# DBBC7505S-F.net
KiCad netlist of a schematic drawn in Altium Designer
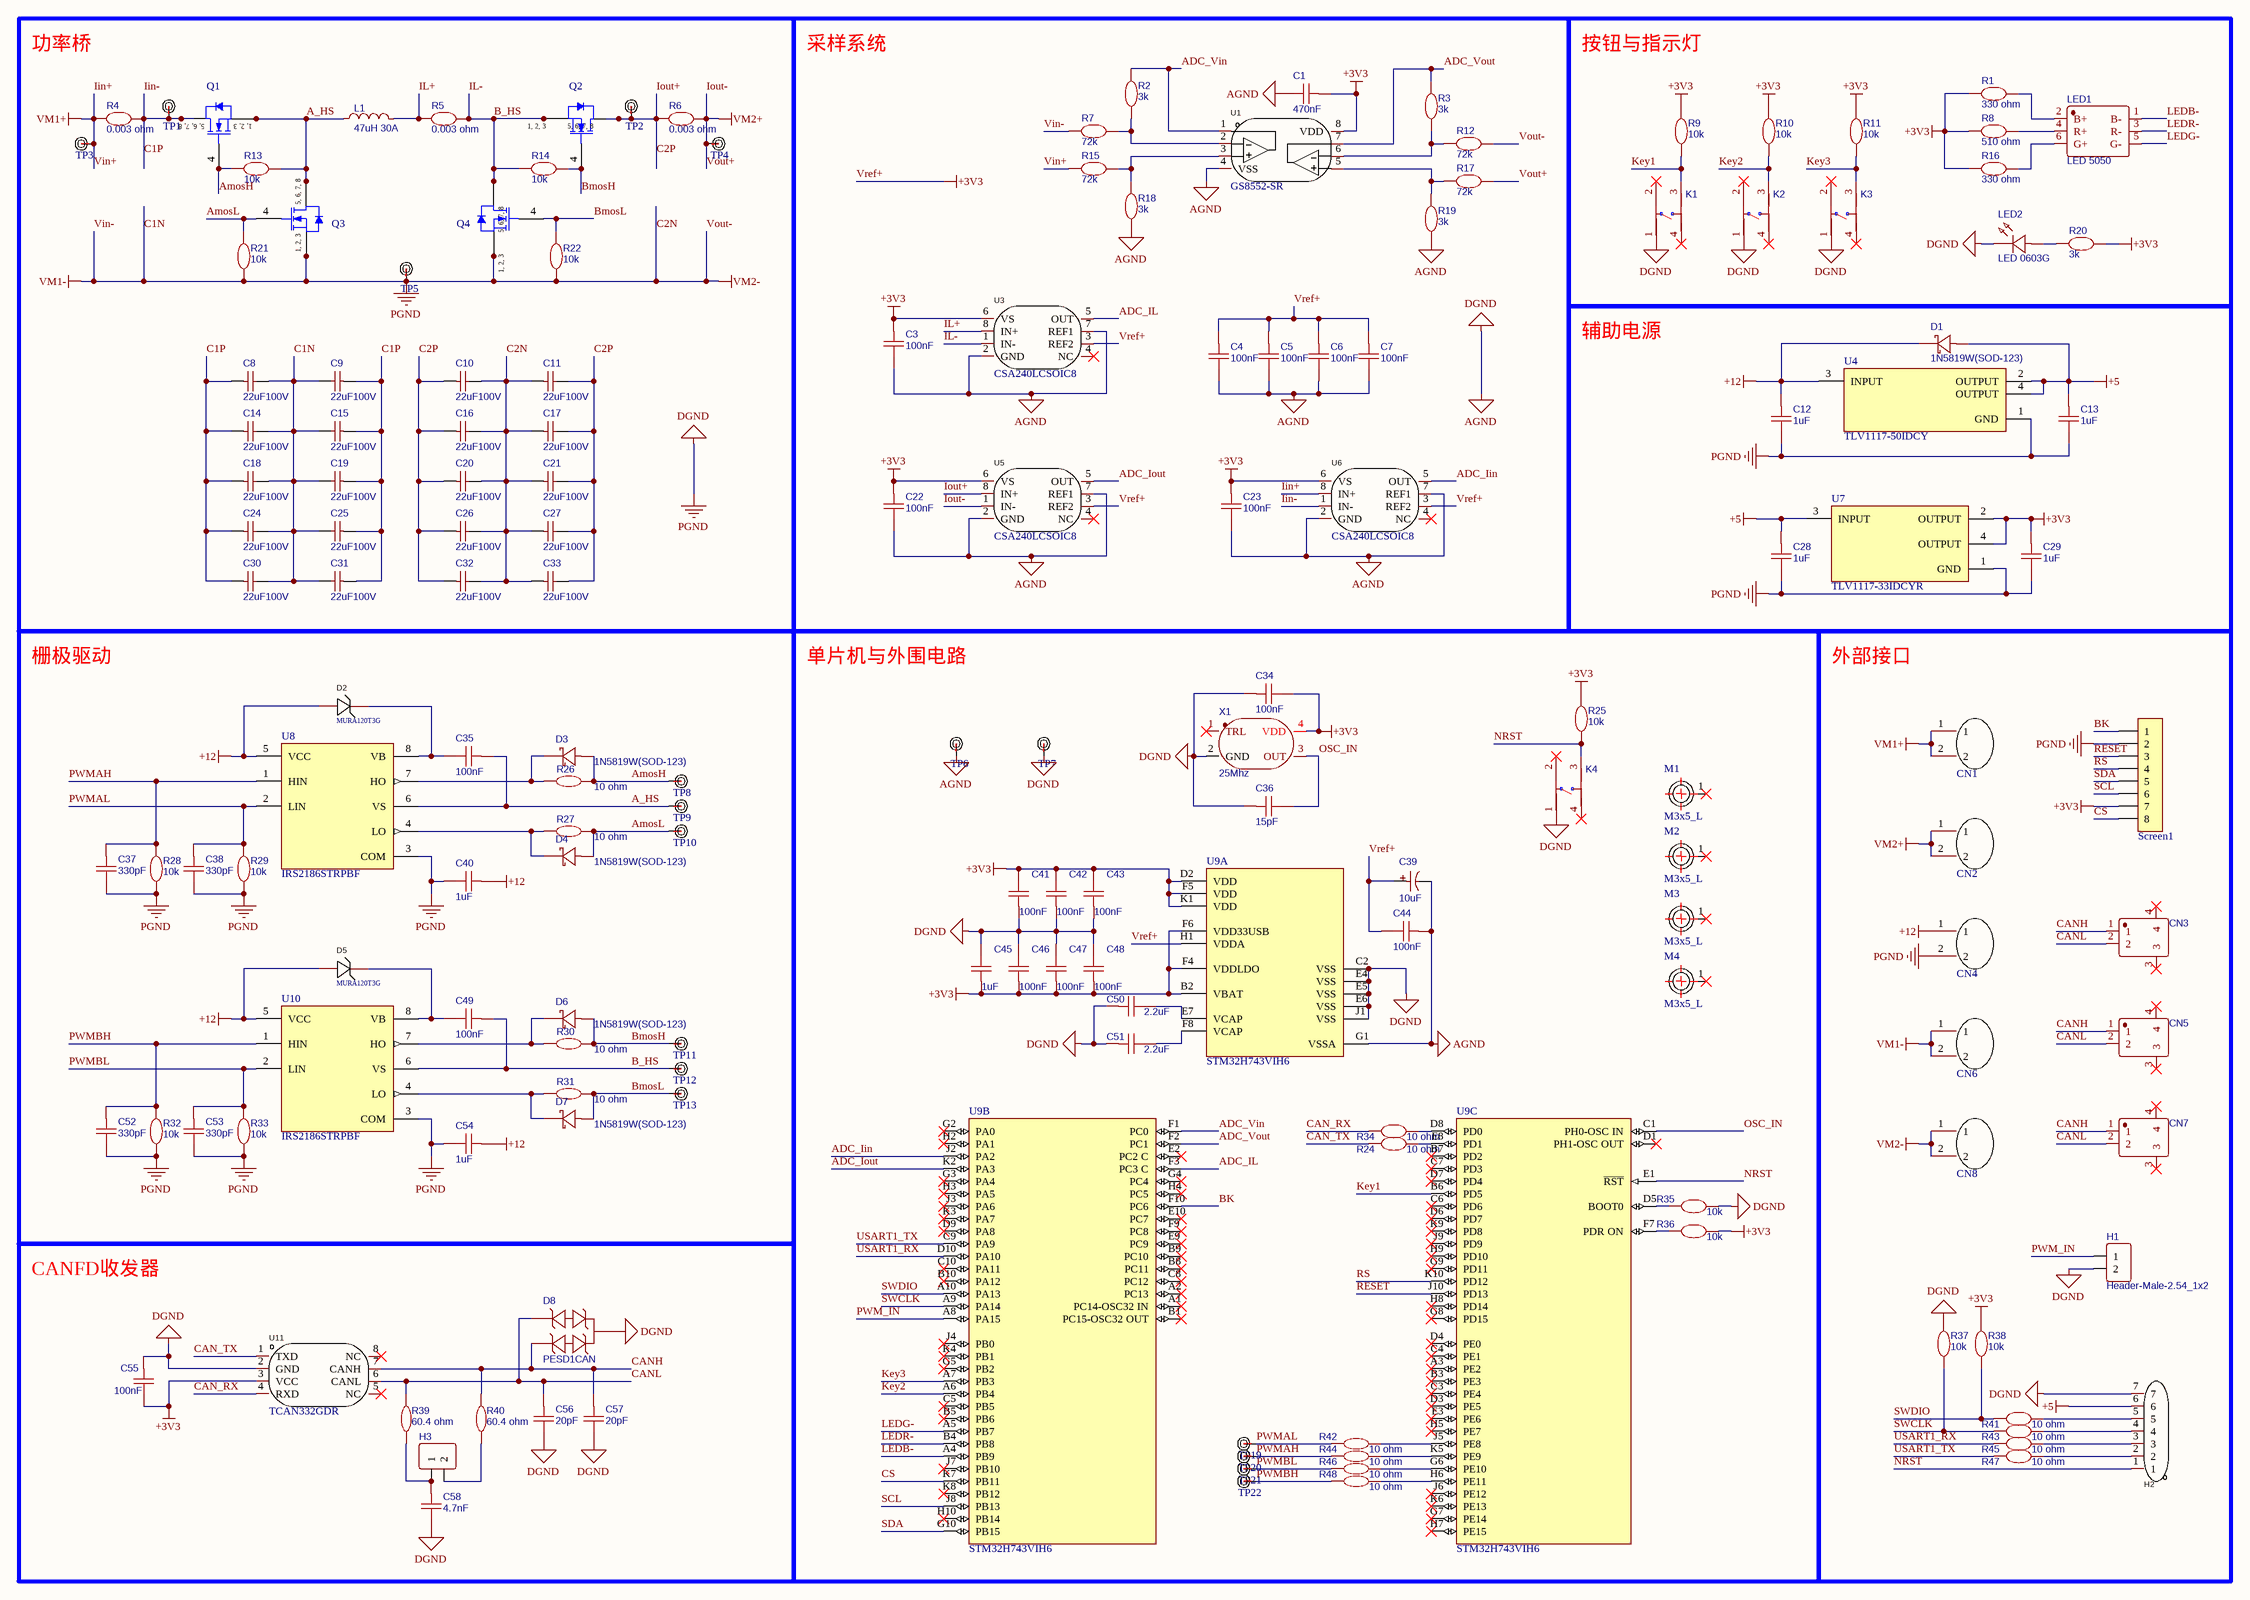
[diagram p0: DBBC7505S-F.SchDoc]

(export (version "E")
  (design (tool "Eeschema 10.0.6"))
  (components
    (comp (ref "C1")
      (value "470nF")
      (footprint "C0402")
      (fields
        (field (name "BOM_MANUFACTURER PART") "CC0402KRX7R7BB104")
        (field (name "BOM_SUPPLIER PART") "C60474")
      )
      (libsource (lib "RC_schlib") (part "C0402"))
    )
    (comp (ref "C3")
      (value "100nF")
      (footprint "C0402")
      (fields
        (field (name "BOM_MANUFACTURER PART") "CC0402KRX7R7BB104")
        (field (name "BOM_SUPPLIER PART") "C60474")
      )
      (libsource (lib "RC_schlib") (part "C0402"))
    )
    (comp (ref "C4")
      (value "100nF")
      (footprint "C0402")
      (fields
        (field (name "BOM_MANUFACTURER PART") "CC0402KRX7R7BB104")
        (field (name "BOM_SUPPLIER PART") "C60474")
      )
      (libsource (lib "RC_schlib") (part "C0402"))
    )
    (comp (ref "C5")
      (value "100nF")
      (footprint "C0402")
      (fields
        (field (name "BOM_MANUFACTURER PART") "CC0402KRX7R7BB104")
        (field (name "BOM_SUPPLIER PART") "C60474")
      )
      (libsource (lib "RC_schlib") (part "C0402"))
    )
    (comp (ref "C6")
      (value "100nF")
      (footprint "C0402")
      (fields
        (field (name "BOM_MANUFACTURER PART") "CC0402KRX7R7BB104")
        (field (name "BOM_SUPPLIER PART") "C60474")
      )
      (libsource (lib "RC_schlib") (part "C0402"))
    )
    (comp (ref "C7")
      (value "100nF")
      (footprint "C0402")
      (fields
        (field (name "BOM_MANUFACTURER PART") "CC0402KRX7R7BB104")
        (field (name "BOM_SUPPLIER PART") "C60474")
      )
      (libsource (lib "RC_schlib") (part "C0402"))
    )
    (comp (ref "C8")
      (value "22uF100V")
      (footprint "C1206")
      (fields
        (field (name "BOM_MANUFACTURER PART") "1206B102K202NT")
        (field (name "BOM_SUPPLIER PART") "C9196")
      )
      (libsource (lib "RC_schlib") (part "C1206"))
    )
    (comp (ref "C9")
      (value "22uF100V")
      (footprint "C1206")
      (fields
        (field (name "BOM_MANUFACTURER PART") "1206B102K202NT")
        (field (name "BOM_SUPPLIER PART") "C9196")
      )
      (libsource (lib "RC_schlib") (part "C1206"))
    )
    (comp (ref "C10")
      (value "22uF100V")
      (footprint "C1206")
      (fields
        (field (name "BOM_MANUFACTURER PART") "1206B102K202NT")
        (field (name "BOM_SUPPLIER PART") "C9196")
      )
      (libsource (lib "RC_schlib") (part "C1206"))
    )
    (comp (ref "C11")
      (value "22uF100V")
      (footprint "C1206")
      (fields
        (field (name "BOM_MANUFACTURER PART") "1206B102K202NT")
        (field (name "BOM_SUPPLIER PART") "C9196")
      )
      (libsource (lib "RC_schlib") (part "C1206"))
    )
    (comp (ref "C12")
      (value "1uF")
      (footprint "C0402")
      (fields
        (field (name "BOM_MANUFACTURER PART") "CC0402KRX7R7BB104")
        (field (name "BOM_SUPPLIER PART") "C60474")
      )
      (libsource (lib "RC_schlib") (part "C0402"))
    )
    (comp (ref "C13")
      (value "1uF")
      (footprint "C0402")
      (fields
        (field (name "BOM_MANUFACTURER PART") "CC0402KRX7R7BB104")
        (field (name "BOM_SUPPLIER PART") "C60474")
      )
      (libsource (lib "RC_schlib") (part "C0402"))
    )
    (comp (ref "C14")
      (value "22uF100V")
      (footprint "C1206")
      (fields
        (field (name "BOM_MANUFACTURER PART") "1206B102K202NT")
        (field (name "BOM_SUPPLIER PART") "C9196")
      )
      (libsource (lib "RC_schlib") (part "C1206"))
    )
    (comp (ref "C15")
      (value "22uF100V")
      (footprint "C1206")
      (fields
        (field (name "BOM_MANUFACTURER PART") "1206B102K202NT")
        (field (name "BOM_SUPPLIER PART") "C9196")
      )
      (libsource (lib "RC_schlib") (part "C1206"))
    )
    (comp (ref "C16")
      (value "22uF100V")
      (footprint "C1206")
      (fields
        (field (name "BOM_MANUFACTURER PART") "1206B102K202NT")
        (field (name "BOM_SUPPLIER PART") "C9196")
      )
      (libsource (lib "RC_schlib") (part "C1206"))
    )
    (comp (ref "C17")
      (value "22uF100V")
      (footprint "C1206")
      (fields
        (field (name "BOM_MANUFACTURER PART") "1206B102K202NT")
        (field (name "BOM_SUPPLIER PART") "C9196")
      )
      (libsource (lib "RC_schlib") (part "C1206"))
    )
    (comp (ref "C18")
      (value "22uF100V")
      (footprint "C1206")
      (fields
        (field (name "BOM_MANUFACTURER PART") "1206B102K202NT")
        (field (name "BOM_SUPPLIER PART") "C9196")
      )
      (libsource (lib "RC_schlib") (part "C1206"))
    )
    (comp (ref "C19")
      (value "22uF100V")
      (footprint "C1206")
      (fields
        (field (name "BOM_MANUFACTURER PART") "1206B102K202NT")
        (field (name "BOM_SUPPLIER PART") "C9196")
      )
      (libsource (lib "RC_schlib") (part "C1206"))
    )
    (comp (ref "C20")
      (value "22uF100V")
      (footprint "C1206")
      (fields
        (field (name "BOM_MANUFACTURER PART") "1206B102K202NT")
        (field (name "BOM_SUPPLIER PART") "C9196")
      )
      (libsource (lib "RC_schlib") (part "C1206"))
    )
    (comp (ref "C21")
      (value "22uF100V")
      (footprint "C1206")
      (fields
        (field (name "BOM_MANUFACTURER PART") "1206B102K202NT")
        (field (name "BOM_SUPPLIER PART") "C9196")
      )
      (libsource (lib "RC_schlib") (part "C1206"))
    )
    (comp (ref "C22")
      (value "100nF")
      (footprint "C0402")
      (fields
        (field (name "BOM_MANUFACTURER PART") "CC0402KRX7R7BB104")
        (field (name "BOM_SUPPLIER PART") "C60474")
      )
      (libsource (lib "RC_schlib") (part "C0402"))
    )
    (comp (ref "C23")
      (value "100nF")
      (footprint "C0402")
      (fields
        (field (name "BOM_MANUFACTURER PART") "CC0402KRX7R7BB104")
        (field (name "BOM_SUPPLIER PART") "C60474")
      )
      (libsource (lib "RC_schlib") (part "C0402"))
    )
    (comp (ref "C24")
      (value "22uF100V")
      (footprint "C1206")
      (fields
        (field (name "BOM_MANUFACTURER PART") "1206B102K202NT")
        (field (name "BOM_SUPPLIER PART") "C9196")
      )
      (libsource (lib "RC_schlib") (part "C1206"))
    )
    (comp (ref "C25")
      (value "22uF100V")
      (footprint "C1206")
      (fields
        (field (name "BOM_MANUFACTURER PART") "1206B102K202NT")
        (field (name "BOM_SUPPLIER PART") "C9196")
      )
      (libsource (lib "RC_schlib") (part "C1206"))
    )
    (comp (ref "C26")
      (value "22uF100V")
      (footprint "C1206")
      (fields
        (field (name "BOM_MANUFACTURER PART") "1206B102K202NT")
        (field (name "BOM_SUPPLIER PART") "C9196")
      )
      (libsource (lib "RC_schlib") (part "C1206"))
    )
    (comp (ref "C27")
      (value "22uF100V")
      (footprint "C1206")
      (fields
        (field (name "BOM_MANUFACTURER PART") "1206B102K202NT")
        (field (name "BOM_SUPPLIER PART") "C9196")
      )
      (libsource (lib "RC_schlib") (part "C1206"))
    )
    (comp (ref "C28")
      (value "1uF")
      (footprint "C0402")
      (fields
        (field (name "BOM_MANUFACTURER PART") "CC0402KRX7R7BB104")
        (field (name "BOM_SUPPLIER PART") "C60474")
      )
      (libsource (lib "RC_schlib") (part "C0402"))
    )
    (comp (ref "C29")
      (value "1uF")
      (footprint "C0402")
      (fields
        (field (name "BOM_MANUFACTURER PART") "CC0402KRX7R7BB104")
        (field (name "BOM_SUPPLIER PART") "C60474")
      )
      (libsource (lib "RC_schlib") (part "C0402"))
    )
    (comp (ref "C30")
      (value "22uF100V")
      (footprint "C1206")
      (fields
        (field (name "BOM_MANUFACTURER PART") "1206B102K202NT")
        (field (name "BOM_SUPPLIER PART") "C9196")
      )
      (libsource (lib "RC_schlib") (part "C1206"))
    )
    (comp (ref "C31")
      (value "22uF100V")
      (footprint "C1206")
      (fields
        (field (name "BOM_MANUFACTURER PART") "1206B102K202NT")
        (field (name "BOM_SUPPLIER PART") "C9196")
      )
      (libsource (lib "RC_schlib") (part "C1206"))
    )
    (comp (ref "C32")
      (value "22uF100V")
      (footprint "C1206")
      (fields
        (field (name "BOM_MANUFACTURER PART") "1206B102K202NT")
        (field (name "BOM_SUPPLIER PART") "C9196")
      )
      (libsource (lib "RC_schlib") (part "C1206"))
    )
    (comp (ref "C33")
      (value "22uF100V")
      (footprint "C1206")
      (fields
        (field (name "BOM_MANUFACTURER PART") "1206B102K202NT")
        (field (name "BOM_SUPPLIER PART") "C9196")
      )
      (libsource (lib "RC_schlib") (part "C1206"))
    )
    (comp (ref "C34")
      (value "100nF")
      (footprint "C0402")
      (fields
        (field (name "BOM_MANUFACTURER PART") "CC0402KRX7R7BB104")
        (field (name "BOM_SUPPLIER PART") "C60474")
      )
      (libsource (lib "RC_schlib") (part "C0402"))
    )
    (comp (ref "C35")
      (value "100nF")
      (footprint "C0402")
      (fields
        (field (name "BOM_MANUFACTURER PART") "CC0402KRX7R7BB104")
        (field (name "BOM_SUPPLIER PART") "C60474")
      )
      (libsource (lib "RC_schlib") (part "C0402"))
    )
    (comp (ref "C36")
      (value "15pF")
      (footprint "C0402")
      (fields
        (field (name "BOM_MANUFACTURER PART") "CC0402KRX7R7BB104")
        (field (name "BOM_SUPPLIER PART") "C60474")
      )
      (libsource (lib "RC_schlib") (part "C0402"))
    )
    (comp (ref "C37")
      (value "330pF")
      (footprint "C0402")
      (fields
        (field (name "BOM_MANUFACTURER PART") "CC0402KRX7R7BB104")
        (field (name "BOM_SUPPLIER PART") "C60474")
      )
      (libsource (lib "RC_schlib") (part "C0402"))
    )
    (comp (ref "C38")
      (value "330pF")
      (footprint "C0402")
      (fields
        (field (name "BOM_MANUFACTURER PART") "CC0402KRX7R7BB104")
        (field (name "BOM_SUPPLIER PART") "C60474")
      )
      (libsource (lib "RC_schlib") (part "C0402"))
    )
    (comp (ref "C39")
      (value "10uF")
      (footprint "CD A(3216)")
      (description "长3.2mm，宽1.6mm，厚1.6mm")
      (fields
        (field (name "BOM_MANUFACTURER PART") "50V 100uF 8X12")
        (field (name "BOM_SUPPLIER PART") "C2749")
      )
      (libsource (lib "eCap_schlib") (part "A型钽电容"))
    )
    (comp (ref "C40")
      (value "1uF")
      (footprint "C0402")
      (fields
        (field (name "BOM_MANUFACTURER PART") "CC0402KRX7R7BB104")
        (field (name "BOM_SUPPLIER PART") "C60474")
      )
      (libsource (lib "RC_schlib") (part "C0402"))
    )
    (comp (ref "C41")
      (value "100nF")
      (footprint "C0402")
      (fields
        (field (name "BOM_MANUFACTURER PART") "CC0402KRX7R7BB104")
        (field (name "BOM_SUPPLIER PART") "C60474")
      )
      (libsource (lib "RC_schlib") (part "C0402"))
    )
    (comp (ref "C42")
      (value "100nF")
      (footprint "C0402")
      (fields
        (field (name "BOM_MANUFACTURER PART") "CC0402KRX7R7BB104")
        (field (name "BOM_SUPPLIER PART") "C60474")
      )
      (libsource (lib "RC_schlib") (part "C0402"))
    )
    (comp (ref "C43")
      (value "100nF")
      (footprint "C0402")
      (fields
        (field (name "BOM_MANUFACTURER PART") "CC0402KRX7R7BB104")
        (field (name "BOM_SUPPLIER PART") "C60474")
      )
      (libsource (lib "RC_schlib") (part "C0402"))
    )
    (comp (ref "C44")
      (value "100nF")
      (footprint "C0402")
      (fields
        (field (name "BOM_MANUFACTURER PART") "CC0402KRX7R7BB104")
        (field (name "BOM_SUPPLIER PART") "C60474")
      )
      (libsource (lib "RC_schlib") (part "C0402"))
    )
    (comp (ref "C45")
      (value "1uF")
      (footprint "C0402")
      (fields
        (field (name "BOM_MANUFACTURER PART") "CC0402KRX7R7BB104")
        (field (name "BOM_SUPPLIER PART") "C60474")
      )
      (libsource (lib "RC_schlib") (part "C0402"))
    )
    (comp (ref "C46")
      (value "100nF")
      (footprint "C0402")
      (fields
        (field (name "BOM_MANUFACTURER PART") "CC0402KRX7R7BB104")
        (field (name "BOM_SUPPLIER PART") "C60474")
      )
      (libsource (lib "RC_schlib") (part "C0402"))
    )
    (comp (ref "C47")
      (value "100nF")
      (footprint "C0402")
      (fields
        (field (name "BOM_MANUFACTURER PART") "CC0402KRX7R7BB104")
        (field (name "BOM_SUPPLIER PART") "C60474")
      )
      (libsource (lib "RC_schlib") (part "C0402"))
    )
    (comp (ref "C48")
      (value "100nF")
      (footprint "C0402")
      (fields
        (field (name "BOM_MANUFACTURER PART") "CC0402KRX7R7BB104")
        (field (name "BOM_SUPPLIER PART") "C60474")
      )
      (libsource (lib "RC_schlib") (part "C0402"))
    )
    (comp (ref "C49")
      (value "100nF")
      (footprint "C0402")
      (fields
        (field (name "BOM_MANUFACTURER PART") "CC0402KRX7R7BB104")
        (field (name "BOM_SUPPLIER PART") "C60474")
      )
      (libsource (lib "RC_schlib") (part "C0402"))
    )
    (comp (ref "C50")
      (value "2.2uF")
      (footprint "C0402")
      (fields
        (field (name "BOM_MANUFACTURER PART") "CC0402KRX7R7BB104")
        (field (name "BOM_SUPPLIER PART") "C60474")
      )
      (libsource (lib "RC_schlib") (part "C0402"))
    )
    (comp (ref "C51")
      (value "2.2uF")
      (footprint "C0402")
      (fields
        (field (name "BOM_MANUFACTURER PART") "CC0402KRX7R7BB104")
        (field (name "BOM_SUPPLIER PART") "C60474")
      )
      (libsource (lib "RC_schlib") (part "C0402"))
    )
    (comp (ref "C52")
      (value "330pF")
      (footprint "C0402")
      (fields
        (field (name "BOM_MANUFACTURER PART") "CC0402KRX7R7BB104")
        (field (name "BOM_SUPPLIER PART") "C60474")
      )
      (libsource (lib "RC_schlib") (part "C0402"))
    )
    (comp (ref "C53")
      (value "330pF")
      (footprint "C0402")
      (fields
        (field (name "BOM_MANUFACTURER PART") "CC0402KRX7R7BB104")
        (field (name "BOM_SUPPLIER PART") "C60474")
      )
      (libsource (lib "RC_schlib") (part "C0402"))
    )
    (comp (ref "C54")
      (value "1uF")
      (footprint "C0402")
      (fields
        (field (name "BOM_MANUFACTURER PART") "CC0402KRX7R7BB104")
        (field (name "BOM_SUPPLIER PART") "C60474")
      )
      (libsource (lib "RC_schlib") (part "C0402"))
    )
    (comp (ref "C55")
      (value "100nF")
      (footprint "C0402")
      (fields
        (field (name "BOM_MANUFACTURER PART") "CC0402KRX7R7BB104")
        (field (name "BOM_SUPPLIER PART") "C60474")
      )
      (libsource (lib "RC_schlib") (part "C0402"))
    )
    (comp (ref "C56")
      (value "20pF")
      (footprint "C0402")
      (fields
        (field (name "BOM_MANUFACTURER PART") "CC0402KRX7R7BB104")
        (field (name "BOM_SUPPLIER PART") "C60474")
      )
      (libsource (lib "RC_schlib") (part "C0402"))
    )
    (comp (ref "C57")
      (value "20pF")
      (footprint "C0402")
      (fields
        (field (name "BOM_MANUFACTURER PART") "CC0402KRX7R7BB104")
        (field (name "BOM_SUPPLIER PART") "C60474")
      )
      (libsource (lib "RC_schlib") (part "C0402"))
    )
    (comp (ref "C58")
      (value "4.7nF")
      (footprint "C0402")
      (fields
        (field (name "BOM_MANUFACTURER PART") "CC0402KRX7R7BB104")
        (field (name "BOM_SUPPLIER PART") "C60474")
      )
      (libsource (lib "RC_schlib") (part "C0402"))
    )
    (comp (ref "CN1")
      (value "1729128")
      (footprint "CONN-TH_2P-P5.08")
      (description "间距:5.08mm;排数:1;每排PIN数:2;安装方式:直针;额定电流:13.5A;额定电压:400V;工作温度范围:-;颜色:绿色;")
      (fields (field (name "MANUFACTURER") "Phoenix Contact(菲尼克斯)"))
      (libsource (lib "MKDSN") (part "MKDSN5.08-2P"))
    )
    (comp (ref "CN2")
      (value "1729128")
      (footprint "CONN-TH_2P-P5.08")
      (description "间距:5.08mm;排数:1;每排PIN数:2;安装方式:直针;额定电流:13.5A;额定电压:400V;工作温度范围:-;颜色:绿色;")
      (fields (field (name "MANUFACTURER") "Phoenix Contact(菲尼克斯)"))
      (libsource (lib "MKDSN") (part "MKDSN5.08-2P"))
    )
    (comp (ref "CN3")
      (value "A1257WR-S-2P")
      (footprint "CONN-SMD_A1257WR-S-2P")
      (fields
        (field (name "BOM_SUPPLIER PART") "C225118")
        (field (name "BOM_MANUFACTURER PART") "A1257WV-S-2P")
        (field (name "CONTRIBUTOR") "LCSC")
      )
      (libsource (lib "GH1.25_schlib") (part "A1257WR-S-2P"))
    )
    (comp (ref "CN4")
      (value "1729128")
      (footprint "CONN-TH_2P-P5.08")
      (description "间距:5.08mm;排数:1;每排PIN数:2;安装方式:直针;额定电流:13.5A;额定电压:400V;工作温度范围:-;颜色:绿色;")
      (fields (field (name "MANUFACTURER") "Phoenix Contact(菲尼克斯)"))
      (libsource (lib "MKDSN") (part "MKDSN5.08-2P"))
    )
    (comp (ref "CN5")
      (value "A1257WR-S-2P")
      (footprint "CONN-SMD_A1257WR-S-2P")
      (fields
        (field (name "BOM_SUPPLIER PART") "C225118")
        (field (name "BOM_MANUFACTURER PART") "A1257WV-S-2P")
        (field (name "CONTRIBUTOR") "LCSC")
      )
      (libsource (lib "GH1.25_schlib") (part "A1257WR-S-2P"))
    )
    (comp (ref "CN6")
      (value "1729128")
      (footprint "CONN-TH_2P-P5.08")
      (description "间距:5.08mm;排数:1;每排PIN数:2;安装方式:直针;额定电流:13.5A;额定电压:400V;工作温度范围:-;颜色:绿色;")
      (fields (field (name "MANUFACTURER") "Phoenix Contact(菲尼克斯)"))
      (libsource (lib "MKDSN") (part "MKDSN5.08-2P"))
    )
    (comp (ref "CN7")
      (value "A1257WR-S-2P")
      (footprint "CONN-SMD_A1257WR-S-2P")
      (fields
        (field (name "BOM_SUPPLIER PART") "C225118")
        (field (name "BOM_MANUFACTURER PART") "A1257WV-S-2P")
        (field (name "CONTRIBUTOR") "LCSC")
      )
      (libsource (lib "GH1.25_schlib") (part "A1257WR-S-2P"))
    )
    (comp (ref "CN8")
      (value "1729128")
      (footprint "CONN-TH_2P-P5.08")
      (description "间距:5.08mm;排数:1;每排PIN数:2;安装方式:直针;额定电流:13.5A;额定电压:400V;工作温度范围:-;颜色:绿色;")
      (fields (field (name "MANUFACTURER") "Phoenix Contact(菲尼克斯)"))
      (libsource (lib "MKDSN") (part "MKDSN5.08-2P"))
    )
    (comp (ref "D1")
      (value "1N5819W(SOD-123)")
      (footprint "SOD-123")
      (fields
        (field (name "BOM_SUPPLIER PART") "C2931787")
        (field (name "BOM_MANUFACTURER PART") "SS34")
        (field (name "CONTRIBUTOR") "LCSC")
      )
      (libsource (lib "Diode_schlib") (part "1N5819W(SOD-123)"))
    )
    (comp (ref "D2")
      (value "MURA120T3G")
      (footprint "SMA")
      (description "25ns 0.875V压降 1A快恢复二极管")
      (fields (field (name "MANUFACTURER") "MDD") (field (name "MANUFACTURER PART") "ES1J"))
      (libsource (lib "Diode_schlib") (part "MURA120T3G"))
    )
    (comp (ref "D3")
      (value "1N5819W(SOD-123)")
      (footprint "SOD-123")
      (fields
        (field (name "BOM_SUPPLIER PART") "C2931787")
        (field (name "BOM_MANUFACTURER PART") "SS34")
        (field (name "CONTRIBUTOR") "LCSC")
      )
      (libsource (lib "Diode_schlib") (part "1N5819W(SOD-123)"))
    )
    (comp (ref "D4")
      (value "1N5819W(SOD-123)")
      (footprint "SOD-123")
      (fields
        (field (name "BOM_SUPPLIER PART") "C2931787")
        (field (name "BOM_MANUFACTURER PART") "SS34")
        (field (name "CONTRIBUTOR") "LCSC")
      )
      (libsource (lib "Diode_schlib") (part "1N5819W(SOD-123)"))
    )
    (comp (ref "D5")
      (value "MURA120T3G")
      (footprint "SMA")
      (description "25ns 0.875V压降 1A快恢复二极管")
      (fields (field (name "MANUFACTURER") "MDD") (field (name "MANUFACTURER PART") "ES1J"))
      (libsource (lib "Diode_schlib") (part "MURA120T3G"))
    )
    (comp (ref "D6")
      (value "1N5819W(SOD-123)")
      (footprint "SOD-123")
      (fields
        (field (name "BOM_SUPPLIER PART") "C2931787")
        (field (name "BOM_MANUFACTURER PART") "SS34")
        (field (name "CONTRIBUTOR") "LCSC")
      )
      (libsource (lib "Diode_schlib") (part "1N5819W(SOD-123)"))
    )
    (comp (ref "D7")
      (value "1N5819W(SOD-123)")
      (footprint "SOD-123")
      (fields
        (field (name "BOM_SUPPLIER PART") "C2931787")
        (field (name "BOM_MANUFACTURER PART") "SS34")
        (field (name "CONTRIBUTOR") "LCSC")
      )
      (libsource (lib "Diode_schlib") (part "1N5819W(SOD-123)"))
    )
    (comp (ref "D8")
      (value "PESD1CAN")
      (footprint "SOT23-3L")
      (fields (field (name "BOM_SUPPLIER PART") "C907838") (field (name "CONTRIBUTOR") "LCSC"))
      (libsource (lib "Diode_schlib") (part "PESD1CAN"))
    )
    (comp (ref "H1")
      (value "Header-Male-2.54_1x2")
      (footprint "HDR2.54-LI-2P")
      (fields
        (field (name "BOM_MANUFACTURER PART") "Header2.54mm 1*3P")
        (field (name "BOM_SUPPLIER PART") "C49257")
      )
      (libsource (lib "2.54CN_schlib") (part "Header-Male-2.54_1x2"))
    )
    (comp (ref "H2")
      (value "7P卧贴排母")
      (footprint "HDR-SMD_7P-P2.54-H-F-L11.5")
      (fields
        (field (name "MANUFACTURER") "XKB Connectivity(中国星坤)")
        (field (name "MANUFACTURER PART") "X6511FRS-06-C85D30")
      )
      (libsource (lib "2.54CN_schlib") (part "7P卧贴排母"))
    )
    (comp (ref "H3")
      (value "Header-Male-2.54_1x2")
      (footprint "HDR2.54-LI-2P")
      (fields
        (field (name "BOM_MANUFACTURER PART") "Header2.54mm 1*3P")
        (field (name "BOM_SUPPLIER PART") "C49257")
      )
      (libsource (lib "2.54CN_schlib") (part "Header-Male-2.54_1x2"))
    )
    (comp (ref "K1")
      (value "TSW SMD-6*6*5")
      (footprint "TSW SMD-6*6*5")
      (fields
        (field (name "BOM_SUPPLIER PART") "C231715")
        (field (name "BOM_MANUFACTURER PART") "KAN0661-1001B")
        (field (name "CONTRIBUTOR") "LCSC")
      )
      (libsource (lib "Button_schlib") (part "TSW SMD-6*6*5"))
    )
    (comp (ref "K2")
      (value "TSW SMD-6*6*5")
      (footprint "TSW SMD-6*6*5")
      (fields
        (field (name "BOM_SUPPLIER PART") "C231715")
        (field (name "BOM_MANUFACTURER PART") "KAN0661-1001B")
        (field (name "CONTRIBUTOR") "LCSC")
      )
      (libsource (lib "Button_schlib") (part "TSW SMD-6*6*5"))
    )
    (comp (ref "K3")
      (value "TSW SMD-6*6*5")
      (footprint "TSW SMD-6*6*5")
      (fields
        (field (name "BOM_SUPPLIER PART") "C231715")
        (field (name "BOM_MANUFACTURER PART") "KAN0661-1001B")
        (field (name "CONTRIBUTOR") "LCSC")
      )
      (libsource (lib "Button_schlib") (part "TSW SMD-6*6*5"))
    )
    (comp (ref "K4")
      (value "TSW SMD-6*6*5")
      (footprint "TSW SMD-6*6*5")
      (fields
        (field (name "BOM_SUPPLIER PART") "C231715")
        (field (name "BOM_MANUFACTURER PART") "KAN0661-1001B")
        (field (name "CONTRIBUTOR") "LCSC")
      )
      (libsource (lib "Button_schlib") (part "TSW SMD-6*6*5"))
    )
    (comp (ref "L1")
      (value "47uH 30A")
      (footprint "106-125卧式")
      (fields
        (field (name "BOM_SUPPLIER PART") "C2936653")
        (field (name "BOM_MANUFACTURER PART") "HA42-4R7MT")
        (field (name "CONTRIBUTOR") "LCSC")
      )
      (libsource (lib "Inductance_schlib") (part "106-125铁硅铝磁环电感"))
    )
    (comp (ref "LED1")
      (value "LED 5050")
      (footprint "LED 5050")
      (description "5050RGB-LED")
      (fields
        (field (name "BOM_SUPPLIER PART") "C3014404")
        (field (name "BOM_MANUFACTURER PART") "11-21/BHC-AQ2S2/2T")
        (field (name "CONTRIBUTOR") "lcsc")
      )
      (libsource (lib "LED_schlib") (part "LED 5050"))
    )
    (comp (ref "LED2")
      (value "LED 0603G")
      (footprint "LED 0603G")
      (description "绿色0603LED")
      (fields
        (field (name "BOM_SUPPLIER PART") "C3014404")
        (field (name "BOM_MANUFACTURER PART") "11-21/BHC-AQ2S2/2T")
        (field (name "CONTRIBUTOR") "lcsc")
      )
      (libsource (lib "LED_schlib") (part "LED 0603G"))
    )
    (comp (ref "M1")
      (value "M3x5_L")
      (footprint "M3x5_L")
      (description "M3铜柱，长：5mm")
      (libsource (lib "M3-CopperPillar_schlib") (part "M3x5_L"))
    )
    (comp (ref "M2")
      (value "M3x5_L")
      (footprint "M3x5_L")
      (description "M3铜柱，长：5mm")
      (libsource (lib "M3-CopperPillar_schlib") (part "M3x5_L"))
    )
    (comp (ref "M3")
      (value "M3x5_L")
      (footprint "M3x5_L")
      (description "M3铜柱，长：5mm")
      (libsource (lib "M3-CopperPillar_schlib") (part "M3x5_L"))
    )
    (comp (ref "M4")
      (value "M3x5_L")
      (footprint "M3x5_L")
      (description "M3铜柱，长：5mm")
      (libsource (lib "M3-CopperPillar_schlib") (part "M3x5_L"))
    )
    (comp (ref "Q1")
      (value "BSC070N10NS3 G")
      (footprint "INF-PG-TDSON-8-1_V")
      (fields
        (field (name "MANUFACTURER") "Infineon")
        (field (name "MANUFACTURER PART NUMBER") "BSC070N10NS3G")
      )
      (libsource (lib "MOSFET_schlib") (part "BSC070N10NS3G"))
    )
    (comp (ref "Q2")
      (value "BSC070N10NS3 G")
      (footprint "INF-PG-TDSON-8-1_V")
      (fields
        (field (name "MANUFACTURER") "Infineon")
        (field (name "MANUFACTURER PART NUMBER") "BSC070N10NS3G")
      )
      (libsource (lib "MOSFET_schlib") (part "BSC070N10NS3G"))
    )
    (comp (ref "Q3")
      (value "BSC070N10NS3 G")
      (footprint "INF-PG-TDSON-8-1_V")
      (fields
        (field (name "MANUFACTURER") "Infineon")
        (field (name "MANUFACTURER PART NUMBER") "BSC070N10NS3G")
      )
      (libsource (lib "MOSFET_schlib") (part "BSC070N10NS3G"))
    )
    (comp (ref "Q4")
      (value "BSC070N10NS3 G")
      (footprint "INF-PG-TDSON-8-1_V")
      (fields
        (field (name "MANUFACTURER") "Infineon")
        (field (name "MANUFACTURER PART NUMBER") "BSC070N10NS3G")
      )
      (libsource (lib "MOSFET_schlib") (part "BSC070N10NS3G"))
    )
    (comp (ref "R1")
      (value "330 ohm")
      (footprint "R0402")
      (fields
        (field (name "BOM_SUPPLIER PART") "C723595")
        (field (name "BOM_MANUFACTURER PART") "SR0402FR-0710KL")
        (field (name "CONTRIBUTOR") "LCSC")
      )
      (libsource (lib "RC_schlib") (part "R0402"))
    )
    (comp (ref "R2")
      (value "3k")
      (footprint "R0402")
      (fields
        (field (name "BOM_SUPPLIER PART") "C723595")
        (field (name "BOM_MANUFACTURER PART") "SR0402FR-0710KL")
        (field (name "CONTRIBUTOR") "LCSC")
      )
      (libsource (lib "RC_schlib") (part "R0402"))
    )
    (comp (ref "R3")
      (value "3k")
      (footprint "R0402")
      (fields
        (field (name "BOM_SUPPLIER PART") "C723595")
        (field (name "BOM_MANUFACTURER PART") "SR0402FR-0710KL")
        (field (name "CONTRIBUTOR") "LCSC")
      )
      (libsource (lib "RC_schlib") (part "R0402"))
    )
    (comp (ref "R4")
      (value "0.003 ohm")
      (footprint "R2512")
      (fields
        (field (name "BOM_SUPPLIER PART") "C375694")
        (field (name "BOM_MANUFACTURER PART") "SR2512FK-0751RL")
        (field (name "CONTRIBUTOR") "LCSC")
      )
      (libsource (lib "RC_schlib") (part "R2512"))
    )
    (comp (ref "R5")
      (value "0.003 ohm")
      (footprint "R2512")
      (fields
        (field (name "BOM_SUPPLIER PART") "C375694")
        (field (name "BOM_MANUFACTURER PART") "SR2512FK-0751RL")
        (field (name "CONTRIBUTOR") "LCSC")
      )
      (libsource (lib "RC_schlib") (part "R2512"))
    )
    (comp (ref "R6")
      (value "0.003 ohm")
      (footprint "R2512")
      (fields
        (field (name "BOM_SUPPLIER PART") "C375694")
        (field (name "BOM_MANUFACTURER PART") "SR2512FK-0751RL")
        (field (name "CONTRIBUTOR") "LCSC")
      )
      (libsource (lib "RC_schlib") (part "R2512"))
    )
    (comp (ref "R7")
      (value "72k")
      (footprint "R0402")
      (fields
        (field (name "BOM_SUPPLIER PART") "C723595")
        (field (name "BOM_MANUFACTURER PART") "SR0402FR-0710KL")
        (field (name "CONTRIBUTOR") "LCSC")
      )
      (libsource (lib "RC_schlib") (part "R0402"))
    )
    (comp (ref "R8")
      (value "510 ohm")
      (footprint "R0402")
      (fields
        (field (name "BOM_SUPPLIER PART") "C723595")
        (field (name "BOM_MANUFACTURER PART") "SR0402FR-0710KL")
        (field (name "CONTRIBUTOR") "LCSC")
      )
      (libsource (lib "RC_schlib") (part "R0402"))
    )
    (comp (ref "R9")
      (value "10k")
      (footprint "R0402")
      (fields
        (field (name "BOM_SUPPLIER PART") "C723595")
        (field (name "BOM_MANUFACTURER PART") "SR0402FR-0710KL")
        (field (name "CONTRIBUTOR") "LCSC")
      )
      (libsource (lib "RC_schlib") (part "R0402"))
    )
    (comp (ref "R10")
      (value "10k")
      (footprint "R0402")
      (fields
        (field (name "BOM_SUPPLIER PART") "C723595")
        (field (name "BOM_MANUFACTURER PART") "SR0402FR-0710KL")
        (field (name "CONTRIBUTOR") "LCSC")
      )
      (libsource (lib "RC_schlib") (part "R0402"))
    )
    (comp (ref "R11")
      (value "10k")
      (footprint "R0402")
      (fields
        (field (name "BOM_SUPPLIER PART") "C723595")
        (field (name "BOM_MANUFACTURER PART") "SR0402FR-0710KL")
        (field (name "CONTRIBUTOR") "LCSC")
      )
      (libsource (lib "RC_schlib") (part "R0402"))
    )
    (comp (ref "R12")
      (value "72k")
      (footprint "R0402")
      (fields
        (field (name "BOM_SUPPLIER PART") "C723595")
        (field (name "BOM_MANUFACTURER PART") "SR0402FR-0710KL")
        (field (name "CONTRIBUTOR") "LCSC")
      )
      (libsource (lib "RC_schlib") (part "R0402"))
    )
    (comp (ref "R13")
      (value "10k")
      (footprint "R0402")
      (fields
        (field (name "BOM_SUPPLIER PART") "C723595")
        (field (name "BOM_MANUFACTURER PART") "SR0402FR-0710KL")
        (field (name "CONTRIBUTOR") "LCSC")
      )
      (libsource (lib "RC_schlib") (part "R0402"))
    )
    (comp (ref "R14")
      (value "10k")
      (footprint "R0402")
      (fields
        (field (name "BOM_SUPPLIER PART") "C723595")
        (field (name "BOM_MANUFACTURER PART") "SR0402FR-0710KL")
        (field (name "CONTRIBUTOR") "LCSC")
      )
      (libsource (lib "RC_schlib") (part "R0402"))
    )
    (comp (ref "R15")
      (value "72k")
      (footprint "R0402")
      (fields
        (field (name "BOM_SUPPLIER PART") "C723595")
        (field (name "BOM_MANUFACTURER PART") "SR0402FR-0710KL")
        (field (name "CONTRIBUTOR") "LCSC")
      )
      (libsource (lib "RC_schlib") (part "R0402"))
    )
    (comp (ref "R16")
      (value "330 ohm")
      (footprint "R0402")
      (fields
        (field (name "BOM_SUPPLIER PART") "C723595")
        (field (name "BOM_MANUFACTURER PART") "SR0402FR-0710KL")
        (field (name "CONTRIBUTOR") "LCSC")
      )
      (libsource (lib "RC_schlib") (part "R0402"))
    )
    (comp (ref "R17")
      (value "72k")
      (footprint "R0402")
      (fields
        (field (name "BOM_SUPPLIER PART") "C723595")
        (field (name "BOM_MANUFACTURER PART") "SR0402FR-0710KL")
        (field (name "CONTRIBUTOR") "LCSC")
      )
      (libsource (lib "RC_schlib") (part "R0402"))
    )
    (comp (ref "R18")
      (value "3k")
      (footprint "R0402")
      (fields
        (field (name "BOM_SUPPLIER PART") "C723595")
        (field (name "BOM_MANUFACTURER PART") "SR0402FR-0710KL")
        (field (name "CONTRIBUTOR") "LCSC")
      )
      (libsource (lib "RC_schlib") (part "R0402"))
    )
    (comp (ref "R19")
      (value "3k")
      (footprint "R0402")
      (fields
        (field (name "BOM_SUPPLIER PART") "C723595")
        (field (name "BOM_MANUFACTURER PART") "SR0402FR-0710KL")
        (field (name "CONTRIBUTOR") "LCSC")
      )
      (libsource (lib "RC_schlib") (part "R0402"))
    )
    (comp (ref "R20")
      (value "3k")
      (footprint "R0402")
      (fields
        (field (name "BOM_SUPPLIER PART") "C723595")
        (field (name "BOM_MANUFACTURER PART") "SR0402FR-0710KL")
        (field (name "CONTRIBUTOR") "LCSC")
      )
      (libsource (lib "RC_schlib") (part "R0402"))
    )
    (comp (ref "R21")
      (value "10k")
      (footprint "R0402")
      (fields
        (field (name "BOM_SUPPLIER PART") "C723595")
        (field (name "BOM_MANUFACTURER PART") "SR0402FR-0710KL")
        (field (name "CONTRIBUTOR") "LCSC")
      )
      (libsource (lib "RC_schlib") (part "R0402"))
    )
    (comp (ref "R22")
      (value "10k")
      (footprint "R0402")
      (fields
        (field (name "BOM_SUPPLIER PART") "C723595")
        (field (name "BOM_MANUFACTURER PART") "SR0402FR-0710KL")
        (field (name "CONTRIBUTOR") "LCSC")
      )
      (libsource (lib "RC_schlib") (part "R0402"))
    )
    (comp (ref "R24")
      (value "10 ohm")
      (footprint "R0402")
      (fields
        (field (name "BOM_SUPPLIER PART") "C723595")
        (field (name "BOM_MANUFACTURER PART") "SR0402FR-0710KL")
        (field (name "CONTRIBUTOR") "LCSC")
      )
      (libsource (lib "RC_schlib") (part "R0402"))
    )
    (comp (ref "R25")
      (value "10k")
      (footprint "R0402")
      (fields
        (field (name "BOM_SUPPLIER PART") "C723595")
        (field (name "BOM_MANUFACTURER PART") "SR0402FR-0710KL")
        (field (name "CONTRIBUTOR") "LCSC")
      )
      (libsource (lib "RC_schlib") (part "R0402"))
    )
    (comp (ref "R26")
      (value "10 ohm")
      (footprint "R0603")
      (fields
        (field (name "BOM_SUPPLIER PART") "C326890")
        (field (name "BOM_MANUFACTURER PART") "SR0603JR-071RL")
        (field (name "CONTRIBUTOR") "LCSC")
      )
      (libsource (lib "RC_schlib") (part "R0603"))
    )
    (comp (ref "R27")
      (value "10 ohm")
      (footprint "R0603")
      (fields
        (field (name "BOM_SUPPLIER PART") "C326890")
        (field (name "BOM_MANUFACTURER PART") "SR0603JR-071RL")
        (field (name "CONTRIBUTOR") "LCSC")
      )
      (libsource (lib "RC_schlib") (part "R0603"))
    )
    (comp (ref "R28")
      (value "10k")
      (footprint "R0402")
      (fields
        (field (name "BOM_SUPPLIER PART") "C723595")
        (field (name "BOM_MANUFACTURER PART") "SR0402FR-0710KL")
        (field (name "CONTRIBUTOR") "LCSC")
      )
      (libsource (lib "RC_schlib") (part "R0402"))
    )
    (comp (ref "R29")
      (value "10k")
      (footprint "R0402")
      (fields
        (field (name "BOM_SUPPLIER PART") "C723595")
        (field (name "BOM_MANUFACTURER PART") "SR0402FR-0710KL")
        (field (name "CONTRIBUTOR") "LCSC")
      )
      (libsource (lib "RC_schlib") (part "R0402"))
    )
    (comp (ref "R30")
      (value "10 ohm")
      (footprint "R0603")
      (fields
        (field (name "BOM_SUPPLIER PART") "C326890")
        (field (name "BOM_MANUFACTURER PART") "SR0603JR-071RL")
        (field (name "CONTRIBUTOR") "LCSC")
      )
      (libsource (lib "RC_schlib") (part "R0603"))
    )
    (comp (ref "R31")
      (value "10 ohm")
      (footprint "R0603")
      (fields
        (field (name "BOM_SUPPLIER PART") "C326890")
        (field (name "BOM_MANUFACTURER PART") "SR0603JR-071RL")
        (field (name "CONTRIBUTOR") "LCSC")
      )
      (libsource (lib "RC_schlib") (part "R0603"))
    )
    (comp (ref "R32")
      (value "10k")
      (footprint "R0402")
      (fields
        (field (name "BOM_SUPPLIER PART") "C723595")
        (field (name "BOM_MANUFACTURER PART") "SR0402FR-0710KL")
        (field (name "CONTRIBUTOR") "LCSC")
      )
      (libsource (lib "RC_schlib") (part "R0402"))
    )
    (comp (ref "R33")
      (value "10k")
      (footprint "R0402")
      (fields
        (field (name "BOM_SUPPLIER PART") "C723595")
        (field (name "BOM_MANUFACTURER PART") "SR0402FR-0710KL")
        (field (name "CONTRIBUTOR") "LCSC")
      )
      (libsource (lib "RC_schlib") (part "R0402"))
    )
    (comp (ref "R34")
      (value "10 ohm")
      (footprint "R0402")
      (fields
        (field (name "BOM_SUPPLIER PART") "C723595")
        (field (name "BOM_MANUFACTURER PART") "SR0402FR-0710KL")
        (field (name "CONTRIBUTOR") "LCSC")
      )
      (libsource (lib "RC_schlib") (part "R0402"))
    )
    (comp (ref "R35")
      (value "10k")
      (footprint "R0402")
      (fields
        (field (name "BOM_SUPPLIER PART") "C723595")
        (field (name "BOM_MANUFACTURER PART") "SR0402FR-0710KL")
        (field (name "CONTRIBUTOR") "LCSC")
      )
      (libsource (lib "RC_schlib") (part "R0402"))
    )
    (comp (ref "R36")
      (value "10k")
      (footprint "R0402")
      (fields
        (field (name "BOM_SUPPLIER PART") "C723595")
        (field (name "BOM_MANUFACTURER PART") "SR0402FR-0710KL")
        (field (name "CONTRIBUTOR") "LCSC")
      )
      (libsource (lib "RC_schlib") (part "R0402"))
    )
    (comp (ref "R37")
      (value "10k")
      (footprint "R0402")
      (fields
        (field (name "BOM_SUPPLIER PART") "C723595")
        (field (name "BOM_MANUFACTURER PART") "SR0402FR-0710KL")
        (field (name "CONTRIBUTOR") "LCSC")
      )
      (libsource (lib "RC_schlib") (part "R0402"))
    )
    (comp (ref "R38")
      (value "10k")
      (footprint "R0402")
      (fields
        (field (name "BOM_SUPPLIER PART") "C723595")
        (field (name "BOM_MANUFACTURER PART") "SR0402FR-0710KL")
        (field (name "CONTRIBUTOR") "LCSC")
      )
      (libsource (lib "RC_schlib") (part "R0402"))
    )
    (comp (ref "R39")
      (value "60.4 ohm")
      (footprint "R0603")
      (fields
        (field (name "BOM_SUPPLIER PART") "C326890")
        (field (name "BOM_MANUFACTURER PART") "SR0603JR-071RL")
        (field (name "CONTRIBUTOR") "LCSC")
      )
      (libsource (lib "RC_schlib") (part "R0603"))
    )
    (comp (ref "R40")
      (value "60.4 ohm")
      (footprint "R0603")
      (fields
        (field (name "BOM_SUPPLIER PART") "C326890")
        (field (name "BOM_MANUFACTURER PART") "SR0603JR-071RL")
        (field (name "CONTRIBUTOR") "LCSC")
      )
      (libsource (lib "RC_schlib") (part "R0603"))
    )
    (comp (ref "R41")
      (value "10 ohm")
      (footprint "R0402")
      (fields
        (field (name "BOM_SUPPLIER PART") "C723595")
        (field (name "BOM_MANUFACTURER PART") "SR0402FR-0710KL")
        (field (name "CONTRIBUTOR") "LCSC")
      )
      (libsource (lib "RC_schlib") (part "R0402"))
    )
    (comp (ref "R42")
      (value "10 ohm")
      (footprint "R0603")
      (fields
        (field (name "BOM_SUPPLIER PART") "C326890")
        (field (name "BOM_MANUFACTURER PART") "SR0603JR-071RL")
        (field (name "CONTRIBUTOR") "LCSC")
      )
      (libsource (lib "RC_schlib") (part "R0603"))
    )
    (comp (ref "R43")
      (value "10 ohm")
      (footprint "R0402")
      (fields
        (field (name "BOM_SUPPLIER PART") "C723595")
        (field (name "BOM_MANUFACTURER PART") "SR0402FR-0710KL")
        (field (name "CONTRIBUTOR") "LCSC")
      )
      (libsource (lib "RC_schlib") (part "R0402"))
    )
    (comp (ref "R44")
      (value "10 ohm")
      (footprint "R0603")
      (fields
        (field (name "BOM_SUPPLIER PART") "C326890")
        (field (name "BOM_MANUFACTURER PART") "SR0603JR-071RL")
        (field (name "CONTRIBUTOR") "LCSC")
      )
      (libsource (lib "RC_schlib") (part "R0603"))
    )
    (comp (ref "R45")
      (value "10 ohm")
      (footprint "R0402")
      (fields
        (field (name "BOM_SUPPLIER PART") "C723595")
        (field (name "BOM_MANUFACTURER PART") "SR0402FR-0710KL")
        (field (name "CONTRIBUTOR") "LCSC")
      )
      (libsource (lib "RC_schlib") (part "R0402"))
    )
    (comp (ref "R46")
      (value "10 ohm")
      (footprint "R0603")
      (fields
        (field (name "BOM_SUPPLIER PART") "C326890")
        (field (name "BOM_MANUFACTURER PART") "SR0603JR-071RL")
        (field (name "CONTRIBUTOR") "LCSC")
      )
      (libsource (lib "RC_schlib") (part "R0603"))
    )
    (comp (ref "R47")
      (value "10 ohm")
      (footprint "R0402")
      (fields
        (field (name "BOM_SUPPLIER PART") "C723595")
        (field (name "BOM_MANUFACTURER PART") "SR0402FR-0710KL")
        (field (name "CONTRIBUTOR") "LCSC")
      )
      (libsource (lib "RC_schlib") (part "R0402"))
    )
    (comp (ref "R48")
      (value "10 ohm")
      (footprint "R0603")
      (fields
        (field (name "BOM_SUPPLIER PART") "C326890")
        (field (name "BOM_MANUFACTURER PART") "SR0603JR-071RL")
        (field (name "CONTRIBUTOR") "LCSC")
      )
      (libsource (lib "RC_schlib") (part "R0603"))
    )
    (comp (ref "Screen1")
      (value "FPC0.5-8P")
      (footprint "FPC0.5 2H-S-W-8P")
      (description "FPC连接器")
      (fields (field (name "版权归属") "黎明电子style"))
      (libsource (lib "FPC_schlib") (part "FPC-8P-0.5"))
    )
    (comp (ref "TP1")
      (value "TestPoint_DIP")
      (footprint "TestPoint_DIP")
      (description "测试点")
      (libsource (lib "M3-CopperPillar_schlib") (part "TestPoint_DIP"))
    )
    (comp (ref "TP2")
      (value "TestPoint_DIP")
      (footprint "TestPoint_DIP")
      (description "测试点")
      (libsource (lib "M3-CopperPillar_schlib") (part "TestPoint_DIP"))
    )
    (comp (ref "TP3")
      (value "TestPoint_DIP")
      (footprint "TestPoint_DIP")
      (description "测试点")
      (libsource (lib "M3-CopperPillar_schlib") (part "TestPoint_DIP"))
    )
    (comp (ref "TP4")
      (value "TestPoint_DIP")
      (footprint "TestPoint_DIP")
      (description "测试点")
      (libsource (lib "M3-CopperPillar_schlib") (part "TestPoint_DIP"))
    )
    (comp (ref "TP5")
      (value "TestPoint_DIP")
      (footprint "TestPoint_DIP")
      (description "测试点")
      (libsource (lib "M3-CopperPillar_schlib") (part "TestPoint_DIP"))
    )
    (comp (ref "TP6")
      (value "TestPoint_DIP")
      (footprint "TestPoint_DIP")
      (description "测试点")
      (libsource (lib "M3-CopperPillar_schlib") (part "TestPoint_DIP"))
    )
    (comp (ref "TP7")
      (value "TestPoint_DIP")
      (footprint "TestPoint_DIP")
      (description "测试点")
      (libsource (lib "M3-CopperPillar_schlib") (part "TestPoint_DIP"))
    )
    (comp (ref "TP8")
      (value "TestPoint_DIP")
      (footprint "TestPoint_DIP")
      (description "测试点")
      (libsource (lib "M3-CopperPillar_schlib") (part "TestPoint_DIP"))
    )
    (comp (ref "TP9")
      (value "TestPoint_DIP")
      (footprint "TestPoint_DIP")
      (description "测试点")
      (libsource (lib "M3-CopperPillar_schlib") (part "TestPoint_DIP"))
    )
    (comp (ref "TP10")
      (value "TestPoint_DIP")
      (footprint "TestPoint_DIP")
      (description "测试点")
      (libsource (lib "M3-CopperPillar_schlib") (part "TestPoint_DIP"))
    )
    (comp (ref "TP11")
      (value "TestPoint_DIP")
      (footprint "TestPoint_DIP")
      (description "测试点")
      (libsource (lib "M3-CopperPillar_schlib") (part "TestPoint_DIP"))
    )
    (comp (ref "TP12")
      (value "TestPoint_DIP")
      (footprint "TestPoint_DIP")
      (description "测试点")
      (libsource (lib "M3-CopperPillar_schlib") (part "TestPoint_DIP"))
    )
    (comp (ref "TP13")
      (value "TestPoint_DIP")
      (footprint "TestPoint_DIP")
      (description "测试点")
      (libsource (lib "M3-CopperPillar_schlib") (part "TestPoint_DIP"))
    )
    (comp (ref "TP19")
      (value "TestPoint_DIP")
      (footprint "TestPoint_DIP")
      (description "测试点")
      (libsource (lib "M3-CopperPillar_schlib") (part "TestPoint_DIP"))
    )
    (comp (ref "TP20")
      (value "TestPoint_DIP")
      (footprint "TestPoint_DIP")
      (description "测试点")
      (libsource (lib "M3-CopperPillar_schlib") (part "TestPoint_DIP"))
    )
    (comp (ref "TP21")
      (value "TestPoint_DIP")
      (footprint "TestPoint_DIP")
      (description "测试点")
      (libsource (lib "M3-CopperPillar_schlib") (part "TestPoint_DIP"))
    )
    (comp (ref "TP22")
      (value "TestPoint_DIP")
      (footprint "TestPoint_DIP")
      (description "测试点")
      (libsource (lib "M3-CopperPillar_schlib") (part "TestPoint_DIP"))
    )
    (comp (ref "U1")
      (value "GS8552-SR")
      (footprint "SOIC-8_L4.9-W3.9-P1.27-LS6.0-BL")
      (description "1.5MHZ, 轨到轨高精双通道运放")
      (fields (field (name "MANUFACTURER") "Gainsil(聚洵)"))
      (libsource (lib "IC_schlib") (part "GS8552-SR"))
    )
    (comp (ref "U3")
      (value "CSA240LCSOIC8")
      (footprint "SOIC-8_L4.9-W3.9-P1.27-LS6.0-BL")
      (description "低噪声低温漂双向电流高端检测芯片")
      (fields (field (name "MANUFACTURER") "analogysemi(类比半导体)"))
      (libsource (lib "IC_schlib") (part "CSA240LCSOIC8"))
    )
    (comp (ref "U4")
      (value "TLV1117-50IDCY")
      (footprint "FP-DCY0004A-MFG")
      (description "IC REG LINEAR 5V 800MA SOT223-4")
      (libsource (lib "Altium Content Vault") (part "e308c0431133a401381f8e374ae96fd"))
    )
    (comp (ref "U5")
      (value "CSA240LCSOIC8")
      (footprint "SOIC-8_L4.9-W3.9-P1.27-LS6.0-BL")
      (description "低噪声低温漂双向电流高端检测芯片")
      (fields (field (name "MANUFACTURER") "analogysemi(类比半导体)"))
      (libsource (lib "IC_schlib") (part "CSA240LCSOIC8"))
    )
    (comp (ref "U6")
      (value "CSA240LCSOIC8")
      (footprint "SOIC-8_L4.9-W3.9-P1.27-LS6.0-BL")
      (description "低噪声低温漂双向电流高端检测芯片")
      (fields (field (name "MANUFACTURER") "analogysemi(类比半导体)"))
      (libsource (lib "IC_schlib") (part "CSA240LCSOIC8"))
    )
    (comp (ref "U7")
      (value "TLV1117-33IDCYR")
      (footprint "FP-DCY0004A-MFG")
      (description "IC REG LIN 3.3V 800MA SOT223-4")
      (fields
        (field (name "MANUFACTURER") "Texas Instruments")
        (field (name "OCTOPART") "https://octopart.com/tlv1117-33idcyr-texas+instruments-669250")
      )
      (libsource (lib "Altium Content Vault") (part "d420fb9686013fb832e66295cdf4acf"))
    )
    (comp (ref "U8")
      (value "IRS2186STRPBF")
      (footprint "FP-PG-DSO-8-IPC_B")
      (description "IC GATE DRVR HI/LOW SIDE 8SOIC")
      (libsource (lib "Altium Content Vault") (part "21f60290e03f1ab215fc746e3cc9a67"))
    )
    (comp (ref "U9")
      (value "STM32H743VIH6")
      (footprint "FP-TFBGA100-A08Q-MFG")
      (description "HIGH-PERFORMANCE AND DSP WITH DP")
      (fields
        (field (name "OCTOPART") "https://octopart.com/stm32h743vih6-stmicroelectronics-93590710")
        (field (name "MANUFACTURER") "STMicroelectronics")
      )
      (libsource (lib "Altium Content Vault") (part "4bc6869135a8923a59641320c1dc386"))
    )
    (comp (ref "U10")
      (value "IRS2186STRPBF")
      (footprint "FP-PG-DSO-8-IPC_B")
      (description "IC GATE DRVR HI/LOW SIDE 8SOIC")
      (libsource (lib "Altium Content Vault") (part "21f60290e03f1ab215fc746e3cc9a67"))
    )
    (comp (ref "U11")
      (value "TCAN332GDR")
      (footprint "SOIC-8_L4.9-W3.9-P1.27-LS6.0-BL")
      (description "CANFD收发芯片")
      (fields (field (name "MANUFACTURER") "TI(德州仪器)"))
      (libsource (lib "IC_schlib") (part "TCAN332GDR"))
    )
    (comp (ref "X1")
      (value "25Mhz")
      (footprint "OSC 3225-4P")
      (fields
        (field (name "BOM_SUPPLIER PART") "C454610")
        (field (name "BOM_MANUFACTURER PART") "TFOM8M4RHKCNT2T")
        (field (name "CONTRIBUTOR") "LCSC")
      )
      (libsource (lib "OSC_schilb") (part "OSC-3225"))
    )
  )
  (nets
    (net (code "1") (name "+3V3") (class "Default")
      (node (ref "C1") (pin "2") (pinfunction "2_2") (pintype "passive"))
      (node (ref "C22") (pin "2") (pinfunction "2_2") (pintype "passive"))
      (node (ref "C23") (pin "2") (pinfunction "2_2") (pintype "passive"))
      (node (ref "C29") (pin "2") (pinfunction "2_2") (pintype "passive"))
      (node (ref "C3") (pin "2") (pinfunction "2_2") (pintype "passive"))
      (node (ref "C34") (pin "1") (pinfunction "1_1") (pintype "passive"))
      (node (ref "C39") (pin "1") (pinfunction "1_1") (pintype "passive"))
      (node (ref "C4") (pin "2") (pinfunction "2_2") (pintype "passive"))
      (node (ref "C41") (pin "1") (pinfunction "1_1") (pintype "passive"))
      (node (ref "C42") (pin "1") (pinfunction "1_1") (pintype "passive"))
      (node (ref "C43") (pin "1") (pinfunction "1_1") (pintype "passive"))
      (node (ref "C44") (pin "1") (pinfunction "1_1") (pintype "passive"))
      (node (ref "C45") (pin "2") (pinfunction "2_2") (pintype "passive"))
      (node (ref "C46") (pin "2") (pinfunction "2_2") (pintype "passive"))
      (node (ref "C47") (pin "2") (pinfunction "2_2") (pintype "passive"))
      (node (ref "C48") (pin "2") (pinfunction "2_2") (pintype "passive"))
      (node (ref "C5") (pin "2") (pinfunction "2_2") (pintype "passive"))
      (node (ref "C55") (pin "1") (pinfunction "1_1") (pintype "passive"))
      (node (ref "C6") (pin "2") (pinfunction "2_2") (pintype "passive"))
      (node (ref "C7") (pin "2") (pinfunction "2_2") (pintype "passive"))
      (node (ref "R1") (pin "2") (pinfunction "2_2") (pintype "passive"))
      (node (ref "R10") (pin "2") (pinfunction "2_2") (pintype "passive"))
      (node (ref "R11") (pin "2") (pinfunction "2_2") (pintype "passive"))
      (node (ref "R16") (pin "1") (pinfunction "1_1") (pintype "passive"))
      (node (ref "R20") (pin "1") (pinfunction "1_1") (pintype "passive"))
      (node (ref "R25") (pin "1") (pinfunction "1_1") (pintype "passive"))
      (node (ref "R36") (pin "1") (pinfunction "1_1") (pintype "passive"))
      (node (ref "R38") (pin "1") (pinfunction "1_1") (pintype "passive"))
      (node (ref "R8") (pin "2") (pinfunction "2_2") (pintype "passive"))
      (node (ref "R9") (pin "2") (pinfunction "2_2") (pintype "passive"))
      (node (ref "Screen1") (pin "7") (pinfunction "7_7") (pintype "passive"))
      (node (ref "U1") (pin "8") (pinfunction "VDD_8") (pintype "passive"))
      (node (ref "U11") (pin "3") (pinfunction "VCC_3") (pintype "passive"))
      (node (ref "U3") (pin "3") (pinfunction "REF2_3") (pintype "passive"))
      (node (ref "U3") (pin "6") (pinfunction "VS_6") (pintype "passive"))
      (node (ref "U5") (pin "3") (pinfunction "REF2_3") (pintype "passive"))
      (node (ref "U5") (pin "6") (pinfunction "VS_6") (pintype "passive"))
      (node (ref "U6") (pin "3") (pinfunction "REF2_3") (pintype "passive"))
      (node (ref "U6") (pin "6") (pinfunction "VS_6") (pintype "passive"))
      (node (ref "U7") (pin "2") (pinfunction "OUTPUT_2") (pintype "power_in"))
      (node (ref "U7") (pin "4") (pinfunction "OUTPUT_4") (pintype "power_in"))
      (node (ref "U9") (pin "B2") (pinfunction "VBAT_B2") (pintype "power_in"))
      (node (ref "U9") (pin "D2") (pinfunction "VDD_D2") (pintype "power_in"))
      (node (ref "U9") (pin "F4") (pinfunction "VDDLDO_F4") (pintype "power_in"))
      (node (ref "U9") (pin "F5") (pinfunction "VDD_F5") (pintype "power_in"))
      (node (ref "U9") (pin "F6") (pinfunction "VDD33USB_F6") (pintype "power_in"))
      (node (ref "U9") (pin "H1") (pinfunction "VDDA_H1") (pintype "power_in"))
      (node (ref "U9") (pin "K1") (pinfunction "VDD_K1") (pintype "power_in"))
      (node (ref "X1") (pin "4") (pinfunction "VDD_4") (pintype "passive"))
    )
    (net (code "2") (name "+5") (class "Default")
      (node (ref "C13") (pin "2") (pinfunction "2_2") (pintype "passive"))
      (node (ref "C28") (pin "2") (pinfunction "2_2") (pintype "passive"))
      (node (ref "D1") (pin "1") (pinfunction "A_1") (pintype "passive"))
      (node (ref "H2") (pin "6") (pinfunction "6_6") (pintype "passive"))
      (node (ref "U4") (pin "2") (pinfunction "OUTPUT_2") (pintype "power_in"))
      (node (ref "U4") (pin "4") (pinfunction "OUTPUT_4") (pintype "power_in"))
      (node (ref "U7") (pin "3") (pinfunction "INPUT_3") (pintype "power_in"))
    )
    (net (code "3") (name "+12") (class "Default")
      (node (ref "C12") (pin "2") (pinfunction "2_2") (pintype "passive"))
      (node (ref "C40") (pin "2") (pinfunction "2_2") (pintype "passive"))
      (node (ref "C54") (pin "2") (pinfunction "2_2") (pintype "passive"))
      (node (ref "CN4") (pin "1") (pinfunction "1_1") (pintype "passive"))
      (node (ref "D1") (pin "2") (pinfunction "K_2") (pintype "passive"))
      (node (ref "D2") (pin "1") (pinfunction "A_1") (pintype "passive"))
      (node (ref "D5") (pin "1") (pinfunction "A_1") (pintype "passive"))
      (node (ref "U10") (pin "5") (pinfunction "VCC_5") (pintype "power_in"))
      (node (ref "U4") (pin "3") (pinfunction "INPUT_3") (pintype "power_in"))
      (node (ref "U8") (pin "5") (pinfunction "VCC_5") (pintype "power_in"))
    )
    (net (code "4") (name "/ADC_IL") (class "Default")
      (node (ref "U3") (pin "5") (pinfunction "OUT_5") (pintype "passive"))
      (node (ref "U9") (pin "F3") (pinfunction "PC3_C_F3") (pintype "bidirectional"))
    )
    (net (code "5") (name "/ADC_Iin") (class "Default")
      (node (ref "U6") (pin "5") (pinfunction "OUT_5") (pintype "passive"))
      (node (ref "U9") (pin "J2") (pinfunction "PA2_J2") (pintype "bidirectional"))
    )
    (net (code "6") (name "/ADC_Iout") (class "Default")
      (node (ref "U5") (pin "5") (pinfunction "OUT_5") (pintype "passive"))
      (node (ref "U9") (pin "K2") (pinfunction "PA3_K2") (pintype "bidirectional"))
    )
    (net (code "7") (name "/ADC_Vin") (class "Default")
      (node (ref "R2") (pin "2") (pinfunction "2_2") (pintype "passive"))
      (node (ref "U1") (pin "1") (pinfunction "OUTA_1") (pintype "passive"))
      (node (ref "U9") (pin "F1") (pinfunction "PC0_F1") (pintype "bidirectional"))
    )
    (net (code "8") (name "/ADC_Vout") (class "Default")
      (node (ref "R3") (pin "2") (pinfunction "2_2") (pintype "passive"))
      (node (ref "U1") (pin "7") (pinfunction "OUTB_7") (pintype "passive"))
      (node (ref "U9") (pin "F2") (pinfunction "PC1_F2") (pintype "bidirectional"))
    )
    (net (code "9") (name "/A_HS") (class "Default")
      (node (ref "C35") (pin "2") (pinfunction "2_2") (pintype "passive"))
      (node (ref "L1") (pin "1") (pinfunction "1_1") (pintype "passive"))
      (node (ref "Q1") (pin "1") (pinfunction "SOURCE_1") (pintype "passive"))
      (node (ref "Q1") (pin "2") (pinfunction "SOURCE_2") (pintype "passive"))
      (node (ref "Q1") (pin "3") (pinfunction "SOURCE_3") (pintype "passive"))
      (node (ref "Q3") (pin "5") (pinfunction "DRAIN_5") (pintype "passive"))
      (node (ref "Q3") (pin "6") (pinfunction "DRAIN_6") (pintype "passive"))
      (node (ref "Q3") (pin "7") (pinfunction "DRAIN_7") (pintype "passive"))
      (node (ref "Q3") (pin "8") (pinfunction "DRAIN_8") (pintype "passive"))
      (node (ref "R13") (pin "2") (pinfunction "2_2") (pintype "passive"))
      (node (ref "TP9") (pin "1") (pinfunction "1_1") (pintype "passive"))
      (node (ref "U8") (pin "6") (pinfunction "VS_6") (pintype "power_in"))
    )
    (net (code "10") (name "/AmosH") (class "Default")
      (node (ref "D3") (pin "1") (pinfunction "A_1") (pintype "passive"))
      (node (ref "Q1") (pin "4") (pinfunction "GATE_4") (pintype "passive"))
      (node (ref "R13") (pin "1") (pinfunction "1_1") (pintype "passive"))
      (node (ref "R26") (pin "2") (pinfunction "2_2") (pintype "passive"))
      (node (ref "TP8") (pin "1") (pinfunction "1_1") (pintype "passive"))
    )
    (net (code "11") (name "/AmosL") (class "Default")
      (node (ref "D4") (pin "1") (pinfunction "A_1") (pintype "passive"))
      (node (ref "Q3") (pin "4") (pinfunction "GATE_4") (pintype "passive"))
      (node (ref "R21") (pin "2") (pinfunction "2_2") (pintype "passive"))
      (node (ref "R27") (pin "2") (pinfunction "2_2") (pintype "passive"))
      (node (ref "TP10") (pin "1") (pinfunction "1_1") (pintype "passive"))
    )
    (net (code "12") (name "/BK") (class "Default")
      (node (ref "Screen1") (pin "1") (pinfunction "1_1") (pintype "passive"))
      (node (ref "U9") (pin "F10") (pinfunction "PC6_F10") (pintype "bidirectional"))
    )
    (net (code "13") (name "/B_HS") (class "Default")
      (node (ref "C49") (pin "2") (pinfunction "2_2") (pintype "passive"))
      (node (ref "Q2") (pin "1") (pinfunction "SOURCE_1") (pintype "passive"))
      (node (ref "Q2") (pin "2") (pinfunction "SOURCE_2") (pintype "passive"))
      (node (ref "Q2") (pin "3") (pinfunction "SOURCE_3") (pintype "passive"))
      (node (ref "Q4") (pin "5") (pinfunction "DRAIN_5") (pintype "passive"))
      (node (ref "Q4") (pin "6") (pinfunction "DRAIN_6") (pintype "passive"))
      (node (ref "Q4") (pin "7") (pinfunction "DRAIN_7") (pintype "passive"))
      (node (ref "Q4") (pin "8") (pinfunction "DRAIN_8") (pintype "passive"))
      (node (ref "R14") (pin "1") (pinfunction "1_1") (pintype "passive"))
      (node (ref "R5") (pin "2") (pinfunction "2_2") (pintype "passive"))
      (node (ref "TP12") (pin "1") (pinfunction "1_1") (pintype "passive"))
      (node (ref "U10") (pin "6") (pinfunction "VS_6") (pintype "power_in"))
      (node (ref "U3") (pin "1") (pinfunction "IN-_1") (pintype "passive"))
    )
    (net (code "14") (name "/BmosH") (class "Default")
      (node (ref "D6") (pin "1") (pinfunction "A_1") (pintype "passive"))
      (node (ref "Q2") (pin "4") (pinfunction "GATE_4") (pintype "passive"))
      (node (ref "R14") (pin "2") (pinfunction "2_2") (pintype "passive"))
      (node (ref "R30") (pin "2") (pinfunction "2_2") (pintype "passive"))
      (node (ref "TP11") (pin "1") (pinfunction "1_1") (pintype "passive"))
    )
    (net (code "15") (name "/BmosL") (class "Default")
      (node (ref "D7") (pin "1") (pinfunction "A_1") (pintype "passive"))
      (node (ref "Q4") (pin "4") (pinfunction "GATE_4") (pintype "passive"))
      (node (ref "R22") (pin "2") (pinfunction "2_2") (pintype "passive"))
      (node (ref "R31") (pin "2") (pinfunction "2_2") (pintype "passive"))
      (node (ref "TP13") (pin "1") (pinfunction "1_1") (pintype "passive"))
    )
    (net (code "16") (name "/C1P") (class "Default")
      (node (ref "C14") (pin "1") (pinfunction "1_1") (pintype "passive"))
      (node (ref "C15") (pin "1") (pinfunction "1_1") (pintype "passive"))
      (node (ref "C18") (pin "1") (pinfunction "1_1") (pintype "passive"))
      (node (ref "C19") (pin "1") (pinfunction "1_1") (pintype "passive"))
      (node (ref "C24") (pin "1") (pinfunction "1_1") (pintype "passive"))
      (node (ref "C25") (pin "1") (pinfunction "1_1") (pintype "passive"))
      (node (ref "C30") (pin "1") (pinfunction "1_1") (pintype "passive"))
      (node (ref "C31") (pin "1") (pinfunction "1_1") (pintype "passive"))
      (node (ref "C8") (pin "1") (pinfunction "1_1") (pintype "passive"))
      (node (ref "C9") (pin "1") (pinfunction "1_1") (pintype "passive"))
      (node (ref "Q1") (pin "5") (pinfunction "DRAIN_5") (pintype "passive"))
      (node (ref "Q1") (pin "6") (pinfunction "DRAIN_6") (pintype "passive"))
      (node (ref "Q1") (pin "7") (pinfunction "DRAIN_7") (pintype "passive"))
      (node (ref "Q1") (pin "8") (pinfunction "DRAIN_8") (pintype "passive"))
      (node (ref "R4") (pin "2") (pinfunction "2_2") (pintype "passive"))
      (node (ref "TP1") (pin "1") (pinfunction "1_1") (pintype "passive"))
      (node (ref "U6") (pin "1") (pinfunction "IN-_1") (pintype "passive"))
    )
    (net (code "17") (name "/C2P") (class "Default")
      (node (ref "C10") (pin "1") (pinfunction "1_1") (pintype "passive"))
      (node (ref "C11") (pin "2") (pinfunction "2_2") (pintype "passive"))
      (node (ref "C16") (pin "1") (pinfunction "1_1") (pintype "passive"))
      (node (ref "C17") (pin "2") (pinfunction "2_2") (pintype "passive"))
      (node (ref "C20") (pin "1") (pinfunction "1_1") (pintype "passive"))
      (node (ref "C21") (pin "2") (pinfunction "2_2") (pintype "passive"))
      (node (ref "C26") (pin "1") (pinfunction "1_1") (pintype "passive"))
      (node (ref "C27") (pin "2") (pinfunction "2_2") (pintype "passive"))
      (node (ref "C32") (pin "1") (pinfunction "1_1") (pintype "passive"))
      (node (ref "C33") (pin "2") (pinfunction "2_2") (pintype "passive"))
      (node (ref "Q2") (pin "5") (pinfunction "DRAIN_5") (pintype "passive"))
      (node (ref "Q2") (pin "6") (pinfunction "DRAIN_6") (pintype "passive"))
      (node (ref "Q2") (pin "7") (pinfunction "DRAIN_7") (pintype "passive"))
      (node (ref "Q2") (pin "8") (pinfunction "DRAIN_8") (pintype "passive"))
      (node (ref "R6") (pin "1") (pinfunction "1_1") (pintype "passive"))
      (node (ref "TP2") (pin "1") (pinfunction "1_1") (pintype "passive"))
      (node (ref "U5") (pin "8") (pinfunction "IN+_8") (pintype "passive"))
    )
    (net (code "18") (name "/CANH") (class "Default")
      (node (ref "C57") (pin "2") (pinfunction "2_2") (pintype "passive"))
      (node (ref "CN3") (pin "1") (pinfunction "1_1") (pintype "passive"))
      (node (ref "CN5") (pin "1") (pinfunction "1_1") (pintype "passive"))
      (node (ref "CN7") (pin "1") (pinfunction "1_1") (pintype "passive"))
      (node (ref "D8") (pin "2") (pinfunction "2_2") (pintype "passive"))
      (node (ref "R40") (pin "2") (pinfunction "2_2") (pintype "passive"))
      (node (ref "U11") (pin "7") (pinfunction "CANH_7") (pintype "passive"))
    )
    (net (code "19") (name "/CANL") (class "Default")
      (node (ref "C56") (pin "2") (pinfunction "2_2") (pintype "passive"))
      (node (ref "CN3") (pin "2") (pinfunction "2_2") (pintype "passive"))
      (node (ref "CN5") (pin "2") (pinfunction "2_2") (pintype "passive"))
      (node (ref "CN7") (pin "2") (pinfunction "2_2") (pintype "passive"))
      (node (ref "D8") (pin "1") (pinfunction "1_1") (pintype "passive"))
      (node (ref "R39") (pin "2") (pinfunction "2_2") (pintype "passive"))
      (node (ref "U11") (pin "6") (pinfunction "CANL_6") (pintype "passive"))
    )
    (net (code "20") (name "/CAN_RX") (class "Default")
      (node (ref "R34") (pin "2") (pinfunction "2_2") (pintype "passive"))
      (node (ref "U11") (pin "4") (pinfunction "RXD_4") (pintype "passive"))
    )
    (net (code "21") (name "/CAN_TX") (class "Default")
      (node (ref "R24") (pin "2") (pinfunction "2_2") (pintype "passive"))
      (node (ref "U11") (pin "1") (pinfunction "TXD_1") (pintype "passive"))
    )
    (net (code "22") (name "/CS") (class "Default")
      (node (ref "Screen1") (pin "8") (pinfunction "8_8") (pintype "passive"))
      (node (ref "U9") (pin "K7") (pinfunction "PB11_K7") (pintype "bidirectional"))
    )
    (net (code "23") (name "/IL+") (class "Default")
      (node (ref "L1") (pin "2") (pinfunction "2_2") (pintype "passive"))
      (node (ref "R5") (pin "1") (pinfunction "1_1") (pintype "passive"))
      (node (ref "U3") (pin "8") (pinfunction "IN+_8") (pintype "passive"))
    )
    (net (code "24") (name "/Key1") (class "Default")
      (node (ref "K1") (pin "3") (pinfunction "3_3") (pintype "passive"))
      (node (ref "R9") (pin "1") (pinfunction "1_1") (pintype "passive"))
      (node (ref "U9") (pin "B6") (pinfunction "PD5_B6") (pintype "bidirectional"))
    )
    (net (code "25") (name "/Key2") (class "Default")
      (node (ref "K2") (pin "3") (pinfunction "3_3") (pintype "passive"))
      (node (ref "R10") (pin "1") (pinfunction "1_1") (pintype "passive"))
      (node (ref "U9") (pin "A6") (pinfunction "PB4_A6") (pintype "bidirectional"))
    )
    (net (code "26") (name "/Key3") (class "Default")
      (node (ref "K3") (pin "3") (pinfunction "3_3") (pintype "passive"))
      (node (ref "R11") (pin "1") (pinfunction "1_1") (pintype "passive"))
      (node (ref "U9") (pin "A7") (pinfunction "PB3_A7") (pintype "bidirectional"))
    )
    (net (code "27") (name "/LEDB-") (class "Default")
      (node (ref "LED1") (pin "1") (pinfunction "B-_1") (pintype "passive"))
      (node (ref "U9") (pin "A4") (pinfunction "PB9_A4") (pintype "bidirectional"))
    )
    (net (code "28") (name "/LEDG-") (class "Default")
      (node (ref "LED1") (pin "5") (pinfunction "G-_5") (pintype "passive"))
      (node (ref "U9") (pin "A5") (pinfunction "PB7_A5") (pintype "bidirectional"))
    )
    (net (code "29") (name "/LEDR-") (class "Default")
      (node (ref "LED1") (pin "3") (pinfunction "R-_3") (pintype "passive"))
      (node (ref "U9") (pin "B4") (pinfunction "PB8_B4") (pintype "bidirectional"))
    )
    (net (code "30") (name "/NRST") (class "Default")
      (node (ref "H2") (pin "1") (pinfunction "1_1") (pintype "passive"))
      (node (ref "K4") (pin "3") (pinfunction "3_3") (pintype "passive"))
      (node (ref "R25") (pin "2") (pinfunction "2_2") (pintype "passive"))
      (node (ref "U9") (pin "E1") (pinfunction "~{RST}_E1") (pintype "input"))
    )
    (net (code "31") (name "/OSC_IN") (class "Default")
      (node (ref "C36") (pin "1") (pinfunction "1_1") (pintype "passive"))
      (node (ref "U9") (pin "C1") (pinfunction "PH0-OSC_IN_C1") (pintype "bidirectional"))
      (node (ref "X1") (pin "3") (pinfunction "OUT_3") (pintype "passive"))
    )
    (net (code "32") (name "/PWMAH") (class "Default")
      (node (ref "C37") (pin "2") (pinfunction "2_2") (pintype "passive"))
      (node (ref "R28") (pin "2") (pinfunction "2_2") (pintype "passive"))
      (node (ref "R44") (pin "2") (pinfunction "2_2") (pintype "passive"))
      (node (ref "TP20") (pin "1") (pinfunction "1_1") (pintype "passive"))
      (node (ref "U8") (pin "1") (pinfunction "HIN_1") (pintype "power_in"))
    )
    (net (code "33") (name "/PWMAL") (class "Default")
      (node (ref "C38") (pin "2") (pinfunction "2_2") (pintype "passive"))
      (node (ref "R29") (pin "2") (pinfunction "2_2") (pintype "passive"))
      (node (ref "R42") (pin "2") (pinfunction "2_2") (pintype "passive"))
      (node (ref "TP19") (pin "1") (pinfunction "1_1") (pintype "passive"))
      (node (ref "U8") (pin "2") (pinfunction "LIN_2") (pintype "power_in"))
    )
    (net (code "34") (name "/PWMBH") (class "Default")
      (node (ref "C52") (pin "2") (pinfunction "2_2") (pintype "passive"))
      (node (ref "R32") (pin "2") (pinfunction "2_2") (pintype "passive"))
      (node (ref "R48") (pin "2") (pinfunction "2_2") (pintype "passive"))
      (node (ref "TP22") (pin "1") (pinfunction "1_1") (pintype "passive"))
      (node (ref "U10") (pin "1") (pinfunction "HIN_1") (pintype "power_in"))
    )
    (net (code "35") (name "/PWMBL") (class "Default")
      (node (ref "C53") (pin "2") (pinfunction "2_2") (pintype "passive"))
      (node (ref "R33") (pin "2") (pinfunction "2_2") (pintype "passive"))
      (node (ref "R46") (pin "2") (pinfunction "2_2") (pintype "passive"))
      (node (ref "TP21") (pin "1") (pinfunction "1_1") (pintype "passive"))
      (node (ref "U10") (pin "2") (pinfunction "LIN_2") (pintype "power_in"))
    )
    (net (code "36") (name "/PWM_IN") (class "Default")
      (node (ref "H1") (pin "1") (pinfunction "1_1") (pintype "passive"))
      (node (ref "U9") (pin "A8") (pinfunction "PA15_A8") (pintype "bidirectional"))
    )
    (net (code "37") (name "/RESET") (class "Default")
      (node (ref "Screen1") (pin "3") (pinfunction "3_3") (pintype "passive"))
      (node (ref "U9") (pin "J10") (pinfunction "PD13_J10") (pintype "bidirectional"))
    )
    (net (code "38") (name "/RS") (class "Default")
      (node (ref "Screen1") (pin "4") (pinfunction "4_4") (pintype "passive"))
      (node (ref "U9") (pin "K10") (pinfunction "PD12_K10") (pintype "bidirectional"))
    )
    (net (code "39") (name "/SCL") (class "Default")
      (node (ref "Screen1") (pin "6") (pinfunction "6_6") (pintype "passive"))
      (node (ref "U9") (pin "J8") (pinfunction "PB13_J8") (pintype "bidirectional"))
    )
    (net (code "40") (name "/SDA") (class "Default")
      (node (ref "Screen1") (pin "5") (pinfunction "5_5") (pintype "passive"))
      (node (ref "U9") (pin "G10") (pinfunction "PB15_G10") (pintype "bidirectional"))
    )
    (net (code "41") (name "/SWCLK") (class "Default")
      (node (ref "R37") (pin "2") (pinfunction "2_2") (pintype "passive"))
      (node (ref "R43") (pin "2") (pinfunction "2_2") (pintype "passive"))
      (node (ref "U9") (pin "A9") (pinfunction "PA14_A9") (pintype "bidirectional"))
    )
    (net (code "42") (name "/SWDIO") (class "Default")
      (node (ref "R38") (pin "2") (pinfunction "2_2") (pintype "passive"))
      (node (ref "R41") (pin "2") (pinfunction "2_2") (pintype "passive"))
      (node (ref "U9") (pin "A10") (pinfunction "PA13_A10") (pintype "bidirectional"))
    )
    (net (code "43") (name "/USART1_RX") (class "Default")
      (node (ref "R45") (pin "2") (pinfunction "2_2") (pintype "passive"))
      (node (ref "U9") (pin "D10") (pinfunction "PA10_D10") (pintype "bidirectional"))
    )
    (net (code "44") (name "/USART1_TX") (class "Default")
      (node (ref "R47") (pin "2") (pinfunction "2_2") (pintype "passive"))
      (node (ref "U9") (pin "C9") (pinfunction "PA9_C9") (pintype "bidirectional"))
    )
    (net (code "45") (name "AGND") (class "Default")
      (node (ref "C1") (pin "1") (pinfunction "1_1") (pintype "passive"))
      (node (ref "C10") (pin "2") (pinfunction "2_2") (pintype "passive"))
      (node (ref "C11") (pin "1") (pinfunction "1_1") (pintype "passive"))
      (node (ref "C12") (pin "1") (pinfunction "1_1") (pintype "passive"))
      (node (ref "C13") (pin "1") (pinfunction "1_1") (pintype "passive"))
      (node (ref "C14") (pin "2") (pinfunction "2_2") (pintype "passive"))
      (node (ref "C15") (pin "2") (pinfunction "2_2") (pintype "passive"))
      (node (ref "C16") (pin "2") (pinfunction "2_2") (pintype "passive"))
      (node (ref "C17") (pin "1") (pinfunction "1_1") (pintype "passive"))
      (node (ref "C18") (pin "2") (pinfunction "2_2") (pintype "passive"))
      (node (ref "C19") (pin "2") (pinfunction "2_2") (pintype "passive"))
      (node (ref "C20") (pin "2") (pinfunction "2_2") (pintype "passive"))
      (node (ref "C21") (pin "1") (pinfunction "1_1") (pintype "passive"))
      (node (ref "C22") (pin "1") (pinfunction "1_1") (pintype "passive"))
      (node (ref "C23") (pin "1") (pinfunction "1_1") (pintype "passive"))
      (node (ref "C24") (pin "2") (pinfunction "2_2") (pintype "passive"))
      (node (ref "C25") (pin "2") (pinfunction "2_2") (pintype "passive"))
      (node (ref "C26") (pin "2") (pinfunction "2_2") (pintype "passive"))
      (node (ref "C27") (pin "1") (pinfunction "1_1") (pintype "passive"))
      (node (ref "C28") (pin "1") (pinfunction "1_1") (pintype "passive"))
      (node (ref "C29") (pin "1") (pinfunction "1_1") (pintype "passive"))
      (node (ref "C3") (pin "1") (pinfunction "1_1") (pintype "passive"))
      (node (ref "C30") (pin "2") (pinfunction "2_2") (pintype "passive"))
      (node (ref "C31") (pin "2") (pinfunction "2_2") (pintype "passive"))
      (node (ref "C32") (pin "2") (pinfunction "2_2") (pintype "passive"))
      (node (ref "C33") (pin "1") (pinfunction "1_1") (pintype "passive"))
      (node (ref "C34") (pin "2") (pinfunction "2_2") (pintype "passive"))
      (node (ref "C36") (pin "2") (pinfunction "2_2") (pintype "passive"))
      (node (ref "C37") (pin "1") (pinfunction "1_1") (pintype "passive"))
      (node (ref "C38") (pin "1") (pinfunction "1_1") (pintype "passive"))
      (node (ref "C39") (pin "2") (pinfunction "2_2") (pintype "passive"))
      (node (ref "C4") (pin "1") (pinfunction "1_1") (pintype "passive"))
      (node (ref "C40") (pin "1") (pinfunction "1_1") (pintype "passive"))
      (node (ref "C41") (pin "2") (pinfunction "2_2") (pintype "passive"))
      (node (ref "C42") (pin "2") (pinfunction "2_2") (pintype "passive"))
      (node (ref "C43") (pin "2") (pinfunction "2_2") (pintype "passive"))
      (node (ref "C44") (pin "2") (pinfunction "2_2") (pintype "passive"))
      (node (ref "C45") (pin "1") (pinfunction "1_1") (pintype "passive"))
      (node (ref "C46") (pin "1") (pinfunction "1_1") (pintype "passive"))
      (node (ref "C47") (pin "1") (pinfunction "1_1") (pintype "passive"))
      (node (ref "C48") (pin "1") (pinfunction "1_1") (pintype "passive"))
      (node (ref "C5") (pin "1") (pinfunction "1_1") (pintype "passive"))
      (node (ref "C50") (pin "2") (pinfunction "2_2") (pintype "passive"))
      (node (ref "C51") (pin "2") (pinfunction "2_2") (pintype "passive"))
      (node (ref "C52") (pin "1") (pinfunction "1_1") (pintype "passive"))
      (node (ref "C53") (pin "1") (pinfunction "1_1") (pintype "passive"))
      (node (ref "C54") (pin "1") (pinfunction "1_1") (pintype "passive"))
      (node (ref "C55") (pin "2") (pinfunction "2_2") (pintype "passive"))
      (node (ref "C56") (pin "1") (pinfunction "1_1") (pintype "passive"))
      (node (ref "C57") (pin "1") (pinfunction "1_1") (pintype "passive"))
      (node (ref "C58") (pin "1") (pinfunction "1_1") (pintype "passive"))
      (node (ref "C6") (pin "1") (pinfunction "1_1") (pintype "passive"))
      (node (ref "C7") (pin "1") (pinfunction "1_1") (pintype "passive"))
      (node (ref "C8") (pin "2") (pinfunction "2_2") (pintype "passive"))
      (node (ref "C9") (pin "2") (pinfunction "2_2") (pintype "passive"))
      (node (ref "CN4") (pin "2") (pinfunction "2_2") (pintype "passive"))
      (node (ref "CN6") (pin "1") (pinfunction "1_1") (pintype "passive"))
      (node (ref "CN6") (pin "2") (pinfunction "2_2") (pintype "passive"))
      (node (ref "CN8") (pin "1") (pinfunction "1_1") (pintype "passive"))
      (node (ref "CN8") (pin "2") (pinfunction "2_2") (pintype "passive"))
      (node (ref "D8") (pin "3") (pinfunction "3_3") (pintype "passive"))
      (node (ref "H1") (pin "2") (pinfunction "2_2") (pintype "passive"))
      (node (ref "H2") (pin "7") (pinfunction "7_7") (pintype "passive"))
      (node (ref "K1") (pin "1") (pinfunction "1_1") (pintype "passive"))
      (node (ref "K2") (pin "1") (pinfunction "1_1") (pintype "passive"))
      (node (ref "K3") (pin "1") (pinfunction "1_1") (pintype "passive"))
      (node (ref "K4") (pin "1") (pinfunction "1_1") (pintype "passive"))
      (node (ref "LED2") (pin "2") (pinfunction "K_2") (pintype "passive"))
      (node (ref "Q3") (pin "1") (pinfunction "SOURCE_1") (pintype "passive"))
      (node (ref "Q3") (pin "2") (pinfunction "SOURCE_2") (pintype "passive"))
      (node (ref "Q3") (pin "3") (pinfunction "SOURCE_3") (pintype "passive"))
      (node (ref "Q4") (pin "1") (pinfunction "SOURCE_1") (pintype "passive"))
      (node (ref "Q4") (pin "2") (pinfunction "SOURCE_2") (pintype "passive"))
      (node (ref "Q4") (pin "3") (pinfunction "SOURCE_3") (pintype "passive"))
      (node (ref "R12") (pin "1") (pinfunction "1_1") (pintype "passive"))
      (node (ref "R18") (pin "1") (pinfunction "1_1") (pintype "passive"))
      (node (ref "R19") (pin "1") (pinfunction "1_1") (pintype "passive"))
      (node (ref "R21") (pin "1") (pinfunction "1_1") (pintype "passive"))
      (node (ref "R22") (pin "1") (pinfunction "1_1") (pintype "passive"))
      (node (ref "R28") (pin "1") (pinfunction "1_1") (pintype "passive"))
      (node (ref "R29") (pin "1") (pinfunction "1_1") (pintype "passive"))
      (node (ref "R32") (pin "1") (pinfunction "1_1") (pintype "passive"))
      (node (ref "R33") (pin "1") (pinfunction "1_1") (pintype "passive"))
      (node (ref "R35") (pin "1") (pinfunction "1_1") (pintype "passive"))
      (node (ref "R37") (pin "1") (pinfunction "1_1") (pintype "passive"))
      (node (ref "R7") (pin "2") (pinfunction "2_2") (pintype "passive"))
      (node (ref "Screen1") (pin "2") (pinfunction "2_2") (pintype "passive"))
      (node (ref "TP5") (pin "1") (pinfunction "1_1") (pintype "passive"))
      (node (ref "TP6") (pin "1") (pinfunction "1_1") (pintype "passive"))
      (node (ref "TP7") (pin "1") (pinfunction "1_1") (pintype "passive"))
      (node (ref "U1") (pin "4") (pinfunction "VSS_4") (pintype "passive"))
      (node (ref "U10") (pin "3") (pinfunction "COM_3") (pintype "passive"))
      (node (ref "U11") (pin "2") (pinfunction "GND_2") (pintype "passive"))
      (node (ref "U3") (pin "2") (pinfunction "GND_2") (pintype "passive"))
      (node (ref "U3") (pin "7") (pinfunction "REF1_7") (pintype "passive"))
      (node (ref "U4") (pin "1") (pinfunction "GND_1") (pintype "power_in"))
      (node (ref "U5") (pin "2") (pinfunction "GND_2") (pintype "passive"))
      (node (ref "U5") (pin "7") (pinfunction "REF1_7") (pintype "passive"))
      (node (ref "U6") (pin "2") (pinfunction "GND_2") (pintype "passive"))
      (node (ref "U6") (pin "7") (pinfunction "REF1_7") (pintype "passive"))
      (node (ref "U7") (pin "1") (pinfunction "GND_1") (pintype "power_in"))
      (node (ref "U8") (pin "3") (pinfunction "COM_3") (pintype "passive"))
      (node (ref "U9") (pin "C2") (pinfunction "VSS_C2") (pintype "power_in"))
      (node (ref "U9") (pin "E4") (pinfunction "VSS_E4") (pintype "power_in"))
      (node (ref "U9") (pin "E5") (pinfunction "VSS_E5") (pintype "power_in"))
      (node (ref "U9") (pin "E6") (pinfunction "VSS_E6") (pintype "power_in"))
      (node (ref "U9") (pin "G1") (pinfunction "VSSA_G1") (pintype "power_in"))
      (node (ref "U9") (pin "J1") (pinfunction "VSS_J1") (pintype "power_in"))
      (node (ref "X1") (pin "2") (pinfunction "GND_2") (pintype "passive"))
    )
    (net (code "46") (name "Net-(C50-Pad1)") (class "Default")
      (node (ref "C50") (pin "1") (pinfunction "1_1") (pintype "passive"))
      (node (ref "U9") (pin "E7") (pinfunction "VCAP_E7") (pintype "power_in"))
    )
    (net (code "47") (name "Net-(C51-Pad1)") (class "Default")
      (node (ref "C51") (pin "1") (pinfunction "1_1") (pintype "passive"))
      (node (ref "U9") (pin "F8") (pinfunction "VCAP_F8") (pintype "power_in"))
    )
    (net (code "48") (name "Net-(C58-Pad2)") (class "Default")
      (node (ref "C58") (pin "2") (pinfunction "2_2") (pintype "passive"))
      (node (ref "H3") (pin "1") (pinfunction "1_1") (pintype "passive"))
      (node (ref "R39") (pin "1") (pinfunction "1_1") (pintype "passive"))
    )
    (net (code "49") (name "Net-(D2-C)") (class "Default")
      (node (ref "C35") (pin "1") (pinfunction "1_1") (pintype "passive"))
      (node (ref "D2") (pin "2") (pinfunction "C_2") (pintype "passive"))
      (node (ref "U8") (pin "8") (pinfunction "VB_8") (pintype "passive"))
    )
    (net (code "50") (name "Net-(D3-K)") (class "Default")
      (node (ref "D3") (pin "2") (pinfunction "K_2") (pintype "passive"))
      (node (ref "R26") (pin "1") (pinfunction "1_1") (pintype "passive"))
      (node (ref "U8") (pin "7") (pinfunction "HO_7") (pintype "output"))
    )
    (net (code "51") (name "Net-(D4-K)") (class "Default")
      (node (ref "D4") (pin "2") (pinfunction "K_2") (pintype "passive"))
      (node (ref "R27") (pin "1") (pinfunction "1_1") (pintype "passive"))
      (node (ref "U8") (pin "4") (pinfunction "LO_4") (pintype "output"))
    )
    (net (code "52") (name "Net-(D5-C)") (class "Default")
      (node (ref "C49") (pin "1") (pinfunction "1_1") (pintype "passive"))
      (node (ref "D5") (pin "2") (pinfunction "C_2") (pintype "passive"))
      (node (ref "U10") (pin "8") (pinfunction "VB_8") (pintype "passive"))
    )
    (net (code "53") (name "Net-(D6-K)") (class "Default")
      (node (ref "D6") (pin "2") (pinfunction "K_2") (pintype "passive"))
      (node (ref "R30") (pin "1") (pinfunction "1_1") (pintype "passive"))
      (node (ref "U10") (pin "7") (pinfunction "HO_7") (pintype "output"))
    )
    (net (code "54") (name "Net-(D7-K)") (class "Default")
      (node (ref "D7") (pin "2") (pinfunction "K_2") (pintype "passive"))
      (node (ref "R31") (pin "1") (pinfunction "1_1") (pintype "passive"))
      (node (ref "U10") (pin "4") (pinfunction "LO_4") (pintype "output"))
    )
    (net (code "55") (name "Net-(H2-Pad2)") (class "Default")
      (node (ref "H2") (pin "2") (pinfunction "2_2") (pintype "passive"))
      (node (ref "R47") (pin "1") (pinfunction "1_1") (pintype "passive"))
    )
    (net (code "56") (name "Net-(H2-Pad3)") (class "Default")
      (node (ref "H2") (pin "3") (pinfunction "3_3") (pintype "passive"))
      (node (ref "R45") (pin "1") (pinfunction "1_1") (pintype "passive"))
    )
    (net (code "57") (name "Net-(H2-Pad4)") (class "Default")
      (node (ref "H2") (pin "4") (pinfunction "4_4") (pintype "passive"))
      (node (ref "R43") (pin "1") (pinfunction "1_1") (pintype "passive"))
    )
    (net (code "58") (name "Net-(H2-Pad5)") (class "Default")
      (node (ref "H2") (pin "5") (pinfunction "5_5") (pintype "passive"))
      (node (ref "R41") (pin "1") (pinfunction "1_1") (pintype "passive"))
    )
    (net (code "59") (name "Net-(H3-Pad2)") (class "Default")
      (node (ref "H3") (pin "2") (pinfunction "2_2") (pintype "passive"))
      (node (ref "R40") (pin "1") (pinfunction "1_1") (pintype "passive"))
    )
    (net (code "60") (name "Net-(LED1-B+)") (class "Default")
      (node (ref "LED1") (pin "2") (pinfunction "B+_2") (pintype "passive"))
      (node (ref "R1") (pin "1") (pinfunction "1_1") (pintype "passive"))
    )
    (net (code "61") (name "Net-(LED1-G+)") (class "Default")
      (node (ref "LED1") (pin "6") (pinfunction "G+_6") (pintype "passive"))
      (node (ref "R16") (pin "2") (pinfunction "2_2") (pintype "passive"))
    )
    (net (code "62") (name "Net-(LED1-R+)") (class "Default")
      (node (ref "LED1") (pin "4") (pinfunction "R+_4") (pintype "passive"))
      (node (ref "R8") (pin "1") (pinfunction "1_1") (pintype "passive"))
    )
    (net (code "63") (name "Net-(LED2-A)") (class "Default")
      (node (ref "LED2") (pin "1") (pinfunction "A_1") (pintype "passive"))
      (node (ref "R20") (pin "2") (pinfunction "2_2") (pintype "passive"))
    )
    (net (code "64") (name "Net-(U1-INA+)") (class "Default")
      (node (ref "R15") (pin "1") (pinfunction "1_1") (pintype "passive"))
      (node (ref "R18") (pin "2") (pinfunction "2_2") (pintype "passive"))
      (node (ref "U1") (pin "3") (pinfunction "INA+_3") (pintype "passive"))
    )
    (net (code "65") (name "Net-(U1-INA-)") (class "Default")
      (node (ref "R2") (pin "1") (pinfunction "1_1") (pintype "passive"))
      (node (ref "R7") (pin "1") (pinfunction "1_1") (pintype "passive"))
      (node (ref "U1") (pin "2") (pinfunction "INA-_2") (pintype "passive"))
    )
    (net (code "66") (name "Net-(U1-INB+)") (class "Default")
      (node (ref "R17") (pin "2") (pinfunction "2_2") (pintype "passive"))
      (node (ref "R19") (pin "2") (pinfunction "2_2") (pintype "passive"))
      (node (ref "U1") (pin "5") (pinfunction "INB+_5") (pintype "passive"))
    )
    (net (code "67") (name "Net-(U1-INB-)") (class "Default")
      (node (ref "R12") (pin "2") (pinfunction "2_2") (pintype "passive"))
      (node (ref "R3") (pin "1") (pinfunction "1_1") (pintype "passive"))
      (node (ref "U1") (pin "6") (pinfunction "INB-_6") (pintype "passive"))
    )
    (net (code "68") (name "Net-(U9C-BOOT0)") (class "Default")
      (node (ref "R35") (pin "2") (pinfunction "2_2") (pintype "passive"))
      (node (ref "U9") (pin "D5") (pinfunction "BOOT0_D5") (pintype "bidirectional"))
    )
    (net (code "69") (name "Net-(U9C-PD0)") (class "Default")
      (node (ref "R34") (pin "1") (pinfunction "1_1") (pintype "passive"))
      (node (ref "U9") (pin "D8") (pinfunction "PD0_D8") (pintype "bidirectional"))
    )
    (net (code "70") (name "Net-(U9C-PD1)") (class "Default")
      (node (ref "R24") (pin "1") (pinfunction "1_1") (pintype "passive"))
      (node (ref "U9") (pin "E8") (pinfunction "PD1_E8") (pintype "bidirectional"))
    )
    (net (code "71") (name "Net-(U9C-PDR_ON)") (class "Default")
      (node (ref "R36") (pin "2") (pinfunction "2_2") (pintype "passive"))
      (node (ref "U9") (pin "F7") (pinfunction "PDR_ON_F7") (pintype "bidirectional"))
    )
    (net (code "72") (name "Net-(U9C-PE8)") (class "Default")
      (node (ref "R42") (pin "1") (pinfunction "1_1") (pintype "passive"))
      (node (ref "U9") (pin "J5") (pinfunction "PE8_J5") (pintype "bidirectional"))
    )
    (net (code "73") (name "Net-(U9C-PE9)") (class "Default")
      (node (ref "R44") (pin "1") (pinfunction "1_1") (pintype "passive"))
      (node (ref "U9") (pin "K5") (pinfunction "PE9_K5") (pintype "bidirectional"))
    )
    (net (code "74") (name "Net-(U9C-PE10)") (class "Default")
      (node (ref "R46") (pin "1") (pinfunction "1_1") (pintype "passive"))
      (node (ref "U9") (pin "G6") (pinfunction "PE10_G6") (pintype "bidirectional"))
    )
    (net (code "75") (name "Net-(U9C-PE11)") (class "Default")
      (node (ref "R48") (pin "1") (pinfunction "1_1") (pintype "passive"))
      (node (ref "U9") (pin "H6") (pinfunction "PE11_H6") (pintype "bidirectional"))
    )
    (net (code "76") (name "VM1+") (class "Default")
      (node (ref "CN1") (pin "1") (pinfunction "1_1") (pintype "passive"))
      (node (ref "CN1") (pin "2") (pinfunction "2_2") (pintype "passive"))
      (node (ref "R15") (pin "2") (pinfunction "2_2") (pintype "passive"))
      (node (ref "R4") (pin "1") (pinfunction "1_1") (pintype "passive"))
      (node (ref "TP3") (pin "1") (pinfunction "1_1") (pintype "passive"))
      (node (ref "U6") (pin "8") (pinfunction "IN+_8") (pintype "passive"))
    )
    (net (code "77") (name "VM2+") (class "Default")
      (node (ref "CN2") (pin "1") (pinfunction "1_1") (pintype "passive"))
      (node (ref "CN2") (pin "2") (pinfunction "2_2") (pintype "passive"))
      (node (ref "R17") (pin "1") (pinfunction "1_1") (pintype "passive"))
      (node (ref "R6") (pin "2") (pinfunction "2_2") (pintype "passive"))
      (node (ref "TP4") (pin "1") (pinfunction "1_1") (pintype "passive"))
      (node (ref "U5") (pin "1") (pinfunction "IN-_1") (pintype "passive"))
    )
    (net (code "78") (name "unconnected-(CN3-Pad3)") (class "Default")
      (node (ref "CN3") (pin "3") (pinfunction "3_3") (pintype "passive+no_connect"))
    )
    (net (code "79") (name "unconnected-(CN3-Pad4)") (class "Default")
      (node (ref "CN3") (pin "4") (pinfunction "4_4") (pintype "passive+no_connect"))
    )
    (net (code "80") (name "unconnected-(CN5-Pad3)") (class "Default")
      (node (ref "CN5") (pin "3") (pinfunction "3_3") (pintype "passive+no_connect"))
    )
    (net (code "81") (name "unconnected-(CN5-Pad4)") (class "Default")
      (node (ref "CN5") (pin "4") (pinfunction "4_4") (pintype "passive+no_connect"))
    )
    (net (code "82") (name "unconnected-(CN7-Pad3)") (class "Default")
      (node (ref "CN7") (pin "3") (pinfunction "3_3") (pintype "passive+no_connect"))
    )
    (net (code "83") (name "unconnected-(CN7-Pad4)") (class "Default")
      (node (ref "CN7") (pin "4") (pinfunction "4_4") (pintype "passive+no_connect"))
    )
    (net (code "84") (name "unconnected-(K1-Pad2)") (class "Default")
      (node (ref "K1") (pin "2") (pinfunction "2_2") (pintype "passive+no_connect"))
    )
    (net (code "85") (name "unconnected-(K1-Pad4)") (class "Default")
      (node (ref "K1") (pin "4") (pinfunction "4_4") (pintype "passive+no_connect"))
    )
    (net (code "86") (name "unconnected-(K2-Pad2)") (class "Default")
      (node (ref "K2") (pin "2") (pinfunction "2_2") (pintype "passive+no_connect"))
    )
    (net (code "87") (name "unconnected-(K2-Pad4)") (class "Default")
      (node (ref "K2") (pin "4") (pinfunction "4_4") (pintype "passive+no_connect"))
    )
    (net (code "88") (name "unconnected-(K3-Pad2)") (class "Default")
      (node (ref "K3") (pin "2") (pinfunction "2_2") (pintype "passive+no_connect"))
    )
    (net (code "89") (name "unconnected-(K3-Pad4)") (class "Default")
      (node (ref "K3") (pin "4") (pinfunction "4_4") (pintype "passive+no_connect"))
    )
    (net (code "90") (name "unconnected-(K4-Pad2)") (class "Default")
      (node (ref "K4") (pin "2") (pinfunction "2_2") (pintype "passive+no_connect"))
    )
    (net (code "91") (name "unconnected-(K4-Pad4)") (class "Default")
      (node (ref "K4") (pin "4") (pinfunction "4_4") (pintype "passive+no_connect"))
    )
    (net (code "92") (name "unconnected-(M1-Pad1)") (class "Default")
      (node (ref "M1") (pin "1") (pinfunction "1_1") (pintype "passive+no_connect"))
    )
    (net (code "93") (name "unconnected-(M2-Pad1)") (class "Default")
      (node (ref "M2") (pin "1") (pinfunction "1_1") (pintype "passive+no_connect"))
    )
    (net (code "94") (name "unconnected-(M3-Pad1)") (class "Default")
      (node (ref "M3") (pin "1") (pinfunction "1_1") (pintype "passive+no_connect"))
    )
    (net (code "95") (name "unconnected-(M4-Pad1)") (class "Default")
      (node (ref "M4") (pin "1") (pinfunction "1_1") (pintype "passive+no_connect"))
    )
    (net (code "96") (name "unconnected-(U3-NC-Pad4)") (class "Default")
      (node (ref "U3") (pin "4") (pinfunction "NC_4") (pintype "passive+no_connect"))
    )
    (net (code "97") (name "unconnected-(U5-NC-Pad4)") (class "Default")
      (node (ref "U5") (pin "4") (pinfunction "NC_4") (pintype "passive+no_connect"))
    )
    (net (code "98") (name "unconnected-(U6-NC-Pad4)") (class "Default")
      (node (ref "U6") (pin "4") (pinfunction "NC_4") (pintype "passive+no_connect"))
    )
    (net (code "99") (name "unconnected-(U9B-PA0-PadG2)") (class "Default")
      (node (ref "U9") (pin "G2") (pinfunction "PA0_G2") (pintype "bidirectional+no_connect"))
    )
    (net (code "100") (name "unconnected-(U9B-PA1-PadH2)") (class "Default")
      (node (ref "U9") (pin "H2") (pinfunction "PA1_H2") (pintype "bidirectional+no_connect"))
    )
    (net (code "101") (name "unconnected-(U9B-PA4-PadG3)") (class "Default")
      (node (ref "U9") (pin "G3") (pinfunction "PA4_G3") (pintype "bidirectional+no_connect"))
    )
    (net (code "102") (name "unconnected-(U9B-PA5-PadH3)") (class "Default")
      (node (ref "U9") (pin "H3") (pinfunction "PA5_H3") (pintype "bidirectional+no_connect"))
    )
    (net (code "103") (name "unconnected-(U9B-PA6-PadJ3)") (class "Default")
      (node (ref "U9") (pin "J3") (pinfunction "PA6_J3") (pintype "bidirectional+no_connect"))
    )
    (net (code "104") (name "unconnected-(U9B-PA7-PadK3)") (class "Default")
      (node (ref "U9") (pin "K3") (pinfunction "PA7_K3") (pintype "bidirectional+no_connect"))
    )
    (net (code "105") (name "unconnected-(U9B-PA8-PadD9)") (class "Default")
      (node (ref "U9") (pin "D9") (pinfunction "PA8_D9") (pintype "bidirectional+no_connect"))
    )
    (net (code "106") (name "unconnected-(U9B-PA11-PadC10)") (class "Default")
      (node (ref "U9") (pin "C10") (pinfunction "PA11_C10") (pintype "bidirectional+no_connect"))
    )
    (net (code "107") (name "unconnected-(U9B-PA12-PadB10)") (class "Default")
      (node (ref "U9") (pin "B10") (pinfunction "PA12_B10") (pintype "bidirectional+no_connect"))
    )
    (net (code "108") (name "unconnected-(U9B-PB0-PadJ4)") (class "Default")
      (node (ref "U9") (pin "J4") (pinfunction "PB0_J4") (pintype "bidirectional+no_connect"))
    )
    (net (code "109") (name "unconnected-(U9B-PB1-PadK4)") (class "Default")
      (node (ref "U9") (pin "K4") (pinfunction "PB1_K4") (pintype "bidirectional+no_connect"))
    )
    (net (code "110") (name "unconnected-(U9B-PB2-PadG5)") (class "Default")
      (node (ref "U9") (pin "G5") (pinfunction "PB2_G5") (pintype "bidirectional+no_connect"))
    )
    (net (code "111") (name "unconnected-(U9B-PB5-PadC5)") (class "Default")
      (node (ref "U9") (pin "C5") (pinfunction "PB5_C5") (pintype "bidirectional+no_connect"))
    )
    (net (code "112") (name "unconnected-(U9B-PB6-PadB5)") (class "Default")
      (node (ref "U9") (pin "B5") (pinfunction "PB6_B5") (pintype "bidirectional+no_connect"))
    )
    (net (code "113") (name "unconnected-(U9B-PB10-PadJ7)") (class "Default")
      (node (ref "U9") (pin "J7") (pinfunction "PB10_J7") (pintype "bidirectional+no_connect"))
    )
    (net (code "114") (name "unconnected-(U9B-PB12-PadK8)") (class "Default")
      (node (ref "U9") (pin "K8") (pinfunction "PB12_K8") (pintype "bidirectional+no_connect"))
    )
    (net (code "115") (name "unconnected-(U9B-PB14-PadH10)") (class "Default")
      (node (ref "U9") (pin "H10") (pinfunction "PB14_H10") (pintype "bidirectional+no_connect"))
    )
    (net (code "116") (name "unconnected-(U9B-PC2_C-PadE2)") (class "Default")
      (node (ref "U9") (pin "E2") (pinfunction "PC2_C_E2") (pintype "bidirectional+no_connect"))
    )
    (net (code "117") (name "unconnected-(U9B-PC4-PadG4)") (class "Default")
      (node (ref "U9") (pin "G4") (pinfunction "PC4_G4") (pintype "bidirectional+no_connect"))
    )
    (net (code "118") (name "unconnected-(U9B-PC5-PadH4)") (class "Default")
      (node (ref "U9") (pin "H4") (pinfunction "PC5_H4") (pintype "bidirectional+no_connect"))
    )
    (net (code "119") (name "unconnected-(U9B-PC7-PadE10)") (class "Default")
      (node (ref "U9") (pin "E10") (pinfunction "PC7_E10") (pintype "bidirectional+no_connect"))
    )
    (net (code "120") (name "unconnected-(U9B-PC8-PadF9)") (class "Default")
      (node (ref "U9") (pin "F9") (pinfunction "PC8_F9") (pintype "bidirectional+no_connect"))
    )
    (net (code "121") (name "unconnected-(U9B-PC9-PadE9)") (class "Default")
      (node (ref "U9") (pin "E9") (pinfunction "PC9_E9") (pintype "bidirectional+no_connect"))
    )
    (net (code "122") (name "unconnected-(U9B-PC10-PadB9)") (class "Default")
      (node (ref "U9") (pin "B9") (pinfunction "PC10_B9") (pintype "bidirectional+no_connect"))
    )
    (net (code "123") (name "unconnected-(U9B-PC11-PadB8)") (class "Default")
      (node (ref "U9") (pin "B8") (pinfunction "PC11_B8") (pintype "bidirectional+no_connect"))
    )
    (net (code "124") (name "unconnected-(U9B-PC12-PadC8)") (class "Default")
      (node (ref "U9") (pin "C8") (pinfunction "PC12_C8") (pintype "bidirectional+no_connect"))
    )
    (net (code "125") (name "unconnected-(U9B-PC13-PadA2)") (class "Default")
      (node (ref "U9") (pin "A2") (pinfunction "PC13_A2") (pintype "bidirectional+no_connect"))
    )
    (net (code "126") (name "unconnected-(U9B-PC14-OSC32_IN-PadA1)") (class "Default")
      (node (ref "U9") (pin "A1") (pinfunction "PC14-OSC32_IN_A1") (pintype "bidirectional+no_connect"))
    )
    (net (code "127") (name "unconnected-(U9B-PC15-OSC32_OUT-PadB1)") (class "Default")
      (node (ref "U9") (pin "B1") (pinfunction "PC15-OSC32_OUT_B1") (pintype "bidirectional+no_connect"))
    )
    (net (code "128") (name "unconnected-(U9C-PD2-PadB7)") (class "Default")
      (node (ref "U9") (pin "B7") (pinfunction "PD2_B7") (pintype "bidirectional+no_connect"))
    )
    (net (code "129") (name "unconnected-(U9C-PD3-PadC7)") (class "Default")
      (node (ref "U9") (pin "C7") (pinfunction "PD3_C7") (pintype "bidirectional+no_connect"))
    )
    (net (code "130") (name "unconnected-(U9C-PD4-PadD7)") (class "Default")
      (node (ref "U9") (pin "D7") (pinfunction "PD4_D7") (pintype "bidirectional+no_connect"))
    )
    (net (code "131") (name "unconnected-(U9C-PD6-PadC6)") (class "Default")
      (node (ref "U9") (pin "C6") (pinfunction "PD6_C6") (pintype "bidirectional+no_connect"))
    )
    (net (code "132") (name "unconnected-(U9C-PD7-PadD6)") (class "Default")
      (node (ref "U9") (pin "D6") (pinfunction "PD7_D6") (pintype "bidirectional+no_connect"))
    )
    (net (code "133") (name "unconnected-(U9C-PD8-PadK9)") (class "Default")
      (node (ref "U9") (pin "K9") (pinfunction "PD8_K9") (pintype "bidirectional+no_connect"))
    )
    (net (code "134") (name "unconnected-(U9C-PD9-PadJ9)") (class "Default")
      (node (ref "U9") (pin "J9") (pinfunction "PD9_J9") (pintype "bidirectional+no_connect"))
    )
    (net (code "135") (name "unconnected-(U9C-PD10-PadH9)") (class "Default")
      (node (ref "U9") (pin "H9") (pinfunction "PD10_H9") (pintype "bidirectional+no_connect"))
    )
    (net (code "136") (name "unconnected-(U9C-PD11-PadG9)") (class "Default")
      (node (ref "U9") (pin "G9") (pinfunction "PD11_G9") (pintype "bidirectional+no_connect"))
    )
    (net (code "137") (name "unconnected-(U9C-PD14-PadH8)") (class "Default")
      (node (ref "U9") (pin "H8") (pinfunction "PD14_H8") (pintype "bidirectional+no_connect"))
    )
    (net (code "138") (name "unconnected-(U9C-PD15-PadG8)") (class "Default")
      (node (ref "U9") (pin "G8") (pinfunction "PD15_G8") (pintype "bidirectional+no_connect"))
    )
    (net (code "139") (name "unconnected-(U9C-PE0-PadD4)") (class "Default")
      (node (ref "U9") (pin "D4") (pinfunction "PE0_D4") (pintype "bidirectional+no_connect"))
    )
    (net (code "140") (name "unconnected-(U9C-PE1-PadC4)") (class "Default")
      (node (ref "U9") (pin "C4") (pinfunction "PE1_C4") (pintype "bidirectional+no_connect"))
    )
    (net (code "141") (name "unconnected-(U9C-PE2-PadA3)") (class "Default")
      (node (ref "U9") (pin "A3") (pinfunction "PE2_A3") (pintype "bidirectional+no_connect"))
    )
    (net (code "142") (name "unconnected-(U9C-PE3-PadB3)") (class "Default")
      (node (ref "U9") (pin "B3") (pinfunction "PE3_B3") (pintype "bidirectional+no_connect"))
    )
    (net (code "143") (name "unconnected-(U9C-PE4-PadC3)") (class "Default")
      (node (ref "U9") (pin "C3") (pinfunction "PE4_C3") (pintype "bidirectional+no_connect"))
    )
    (net (code "144") (name "unconnected-(U9C-PE5-PadD3)") (class "Default")
      (node (ref "U9") (pin "D3") (pinfunction "PE5_D3") (pintype "bidirectional+no_connect"))
    )
    (net (code "145") (name "unconnected-(U9C-PE6-PadE3)") (class "Default")
      (node (ref "U9") (pin "E3") (pinfunction "PE6_E3") (pintype "bidirectional+no_connect"))
    )
    (net (code "146") (name "unconnected-(U9C-PE7-PadH5)") (class "Default")
      (node (ref "U9") (pin "H5") (pinfunction "PE7_H5") (pintype "bidirectional+no_connect"))
    )
    (net (code "147") (name "unconnected-(U9C-PE12-PadJ6)") (class "Default")
      (node (ref "U9") (pin "J6") (pinfunction "PE12_J6") (pintype "bidirectional+no_connect"))
    )
    (net (code "148") (name "unconnected-(U9C-PE13-PadK6)") (class "Default")
      (node (ref "U9") (pin "K6") (pinfunction "PE13_K6") (pintype "bidirectional+no_connect"))
    )
    (net (code "149") (name "unconnected-(U9C-PE14-PadG7)") (class "Default")
      (node (ref "U9") (pin "G7") (pinfunction "PE14_G7") (pintype "bidirectional+no_connect"))
    )
    (net (code "150") (name "unconnected-(U9C-PE15-PadH7)") (class "Default")
      (node (ref "U9") (pin "H7") (pinfunction "PE15_H7") (pintype "bidirectional+no_connect"))
    )
    (net (code "151") (name "unconnected-(U9C-PH1-OSC_OUT-PadD1)") (class "Default")
      (node (ref "U9") (pin "D1") (pinfunction "PH1-OSC_OUT_D1") (pintype "bidirectional+no_connect"))
    )
    (net (code "152") (name "unconnected-(U11-NC-Pad5)") (class "Default")
      (node (ref "U11") (pin "5") (pinfunction "NC_5") (pintype "passive+no_connect"))
    )
    (net (code "153") (name "unconnected-(U11-NC-Pad8)") (class "Default")
      (node (ref "U11") (pin "8") (pinfunction "NC_8") (pintype "passive+no_connect"))
    )
    (net (code "154") (name "unconnected-(X1-TRL-Pad1)") (class "Default")
      (node (ref "X1") (pin "1") (pinfunction "TRL_1") (pintype "passive+no_connect"))
    )
  )
)
